# LAUNCHXL-TMS57004_RevB.net
KiCad netlist of a schematic drawn in EAGLE
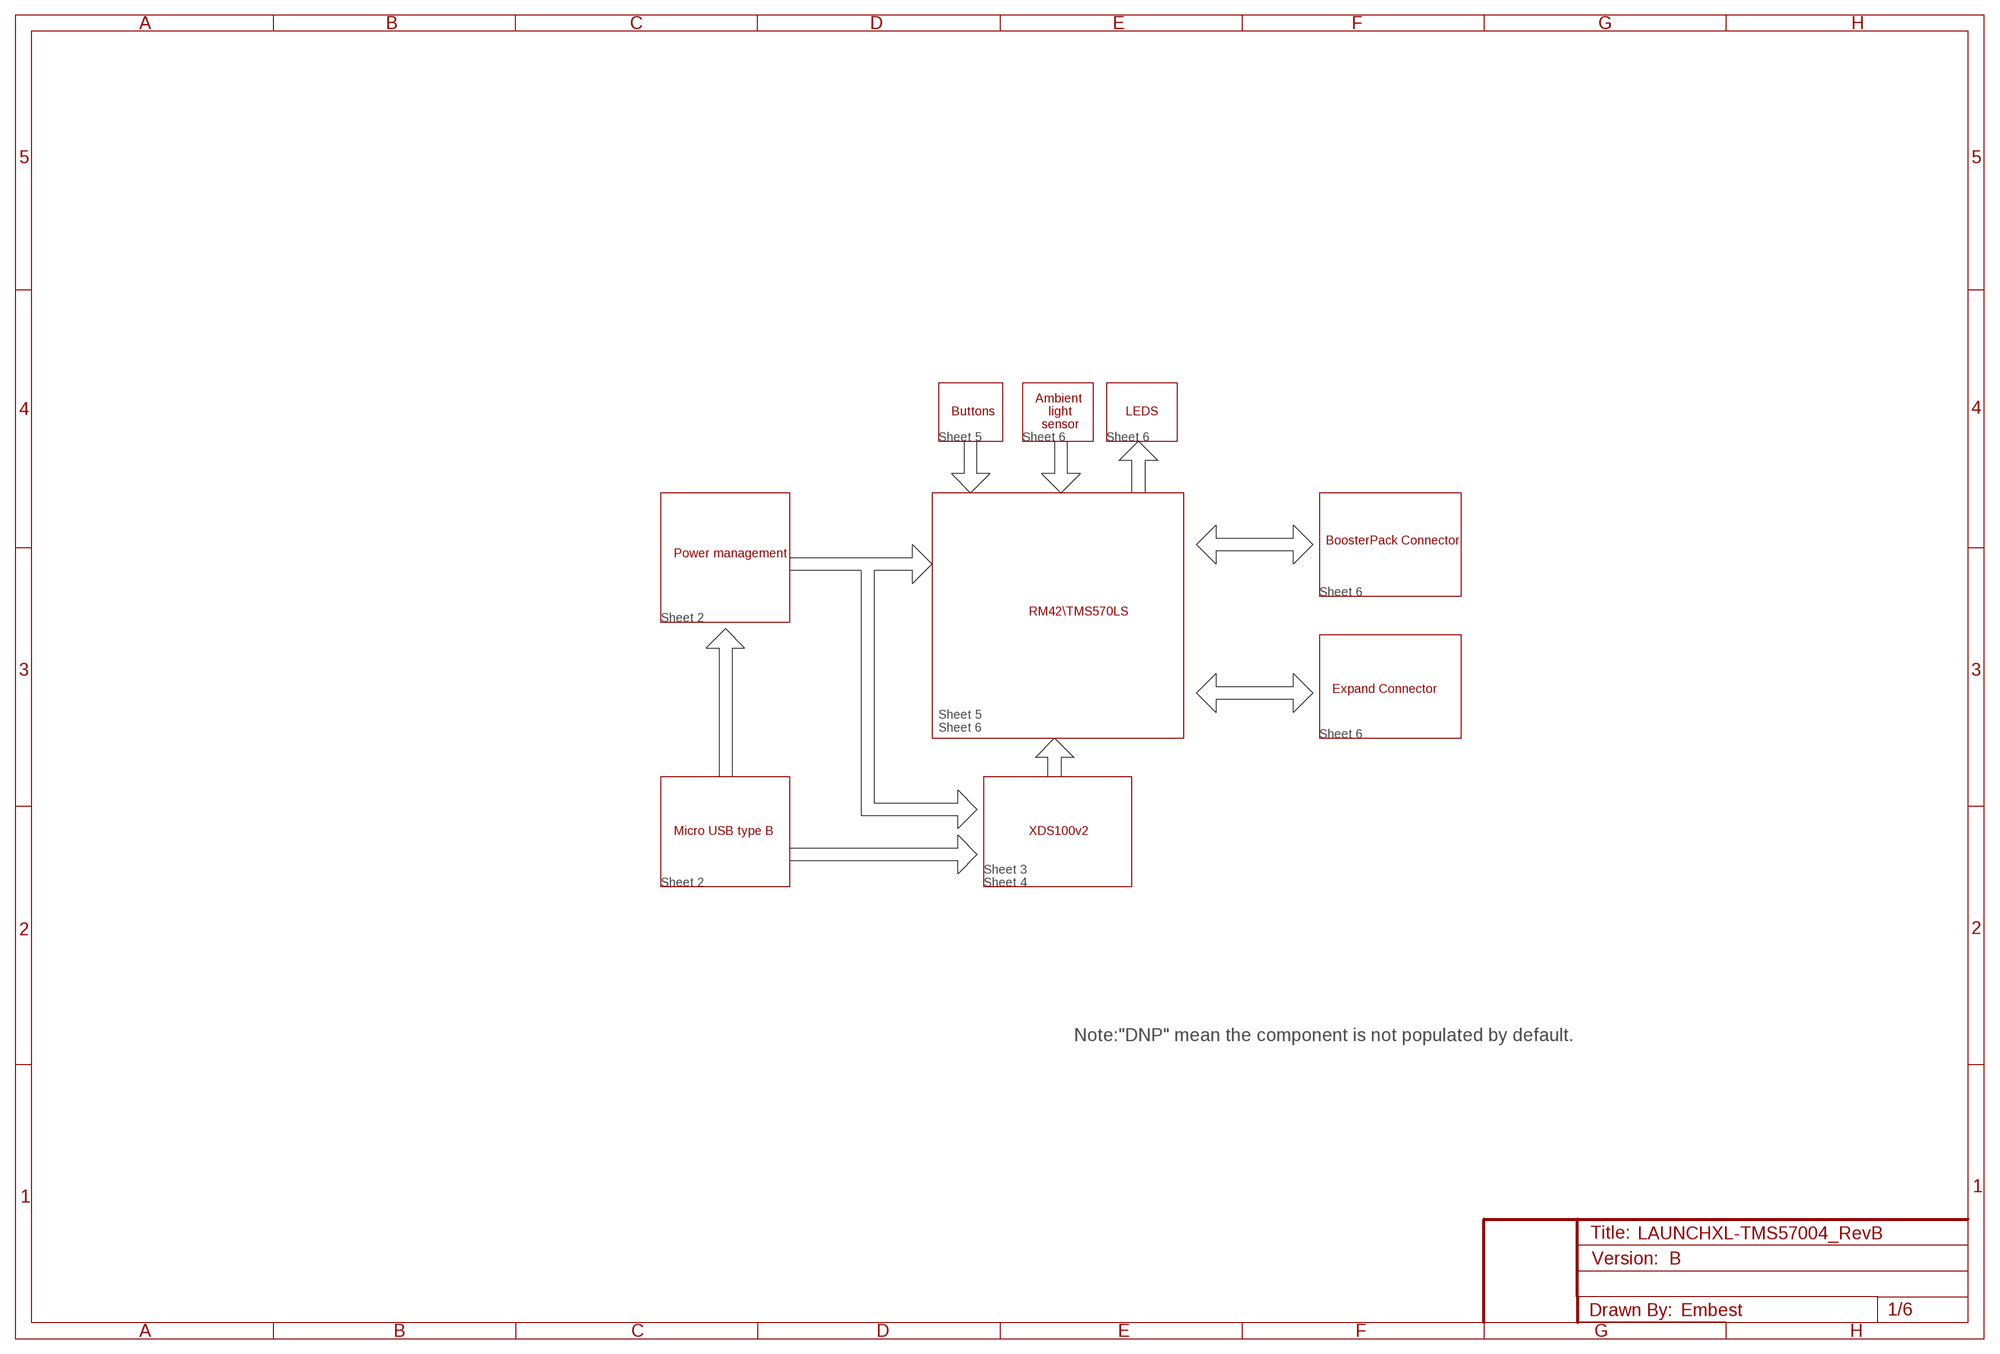
[diagram p0: schematic, sheet 1]
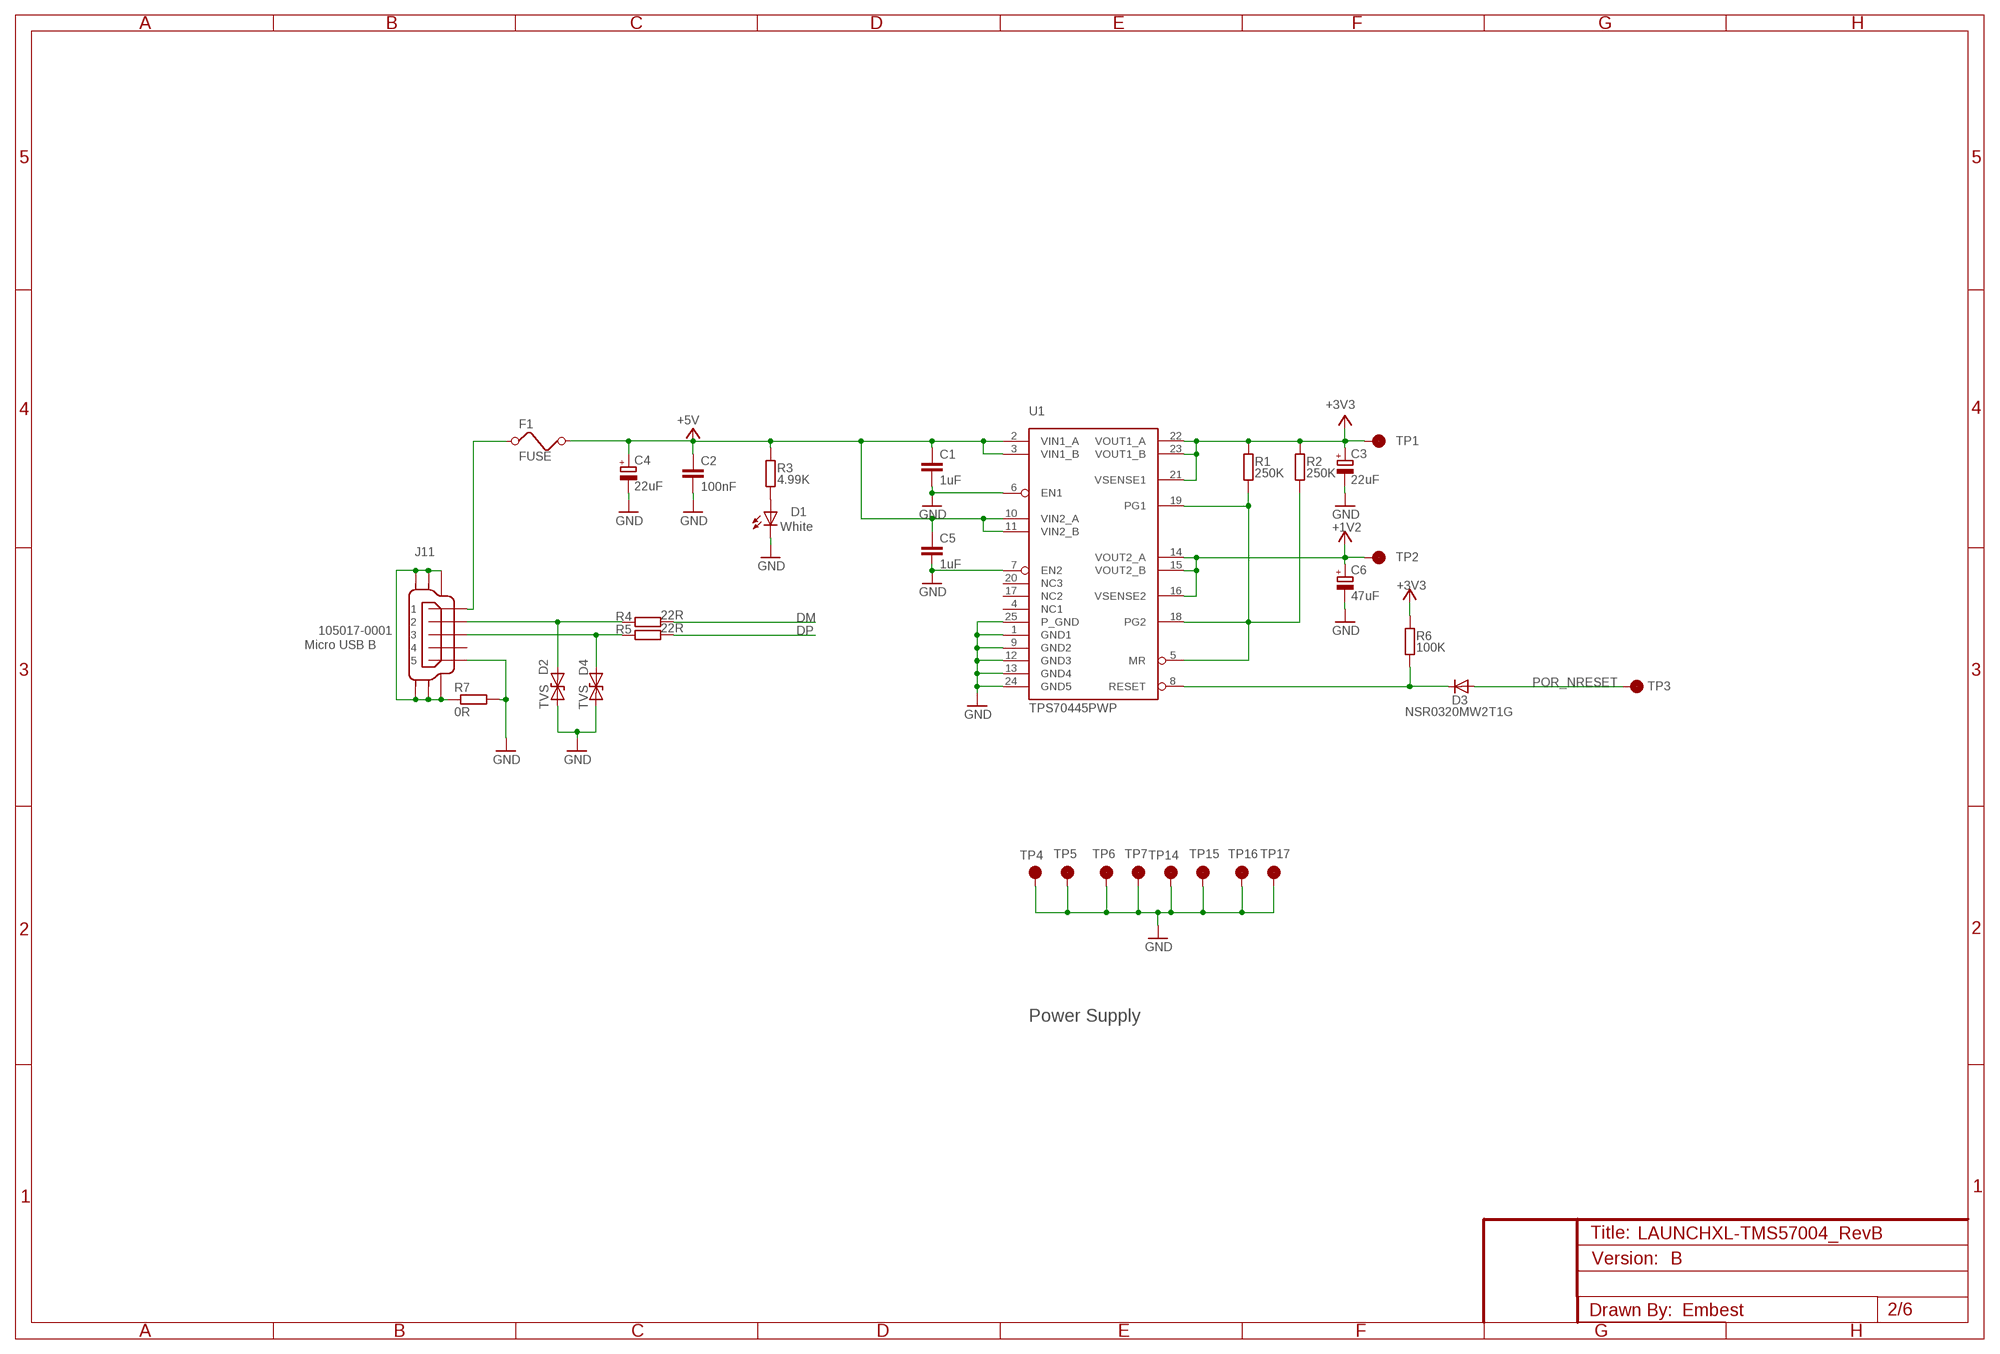
[diagram p1: schematic, sheet 2]
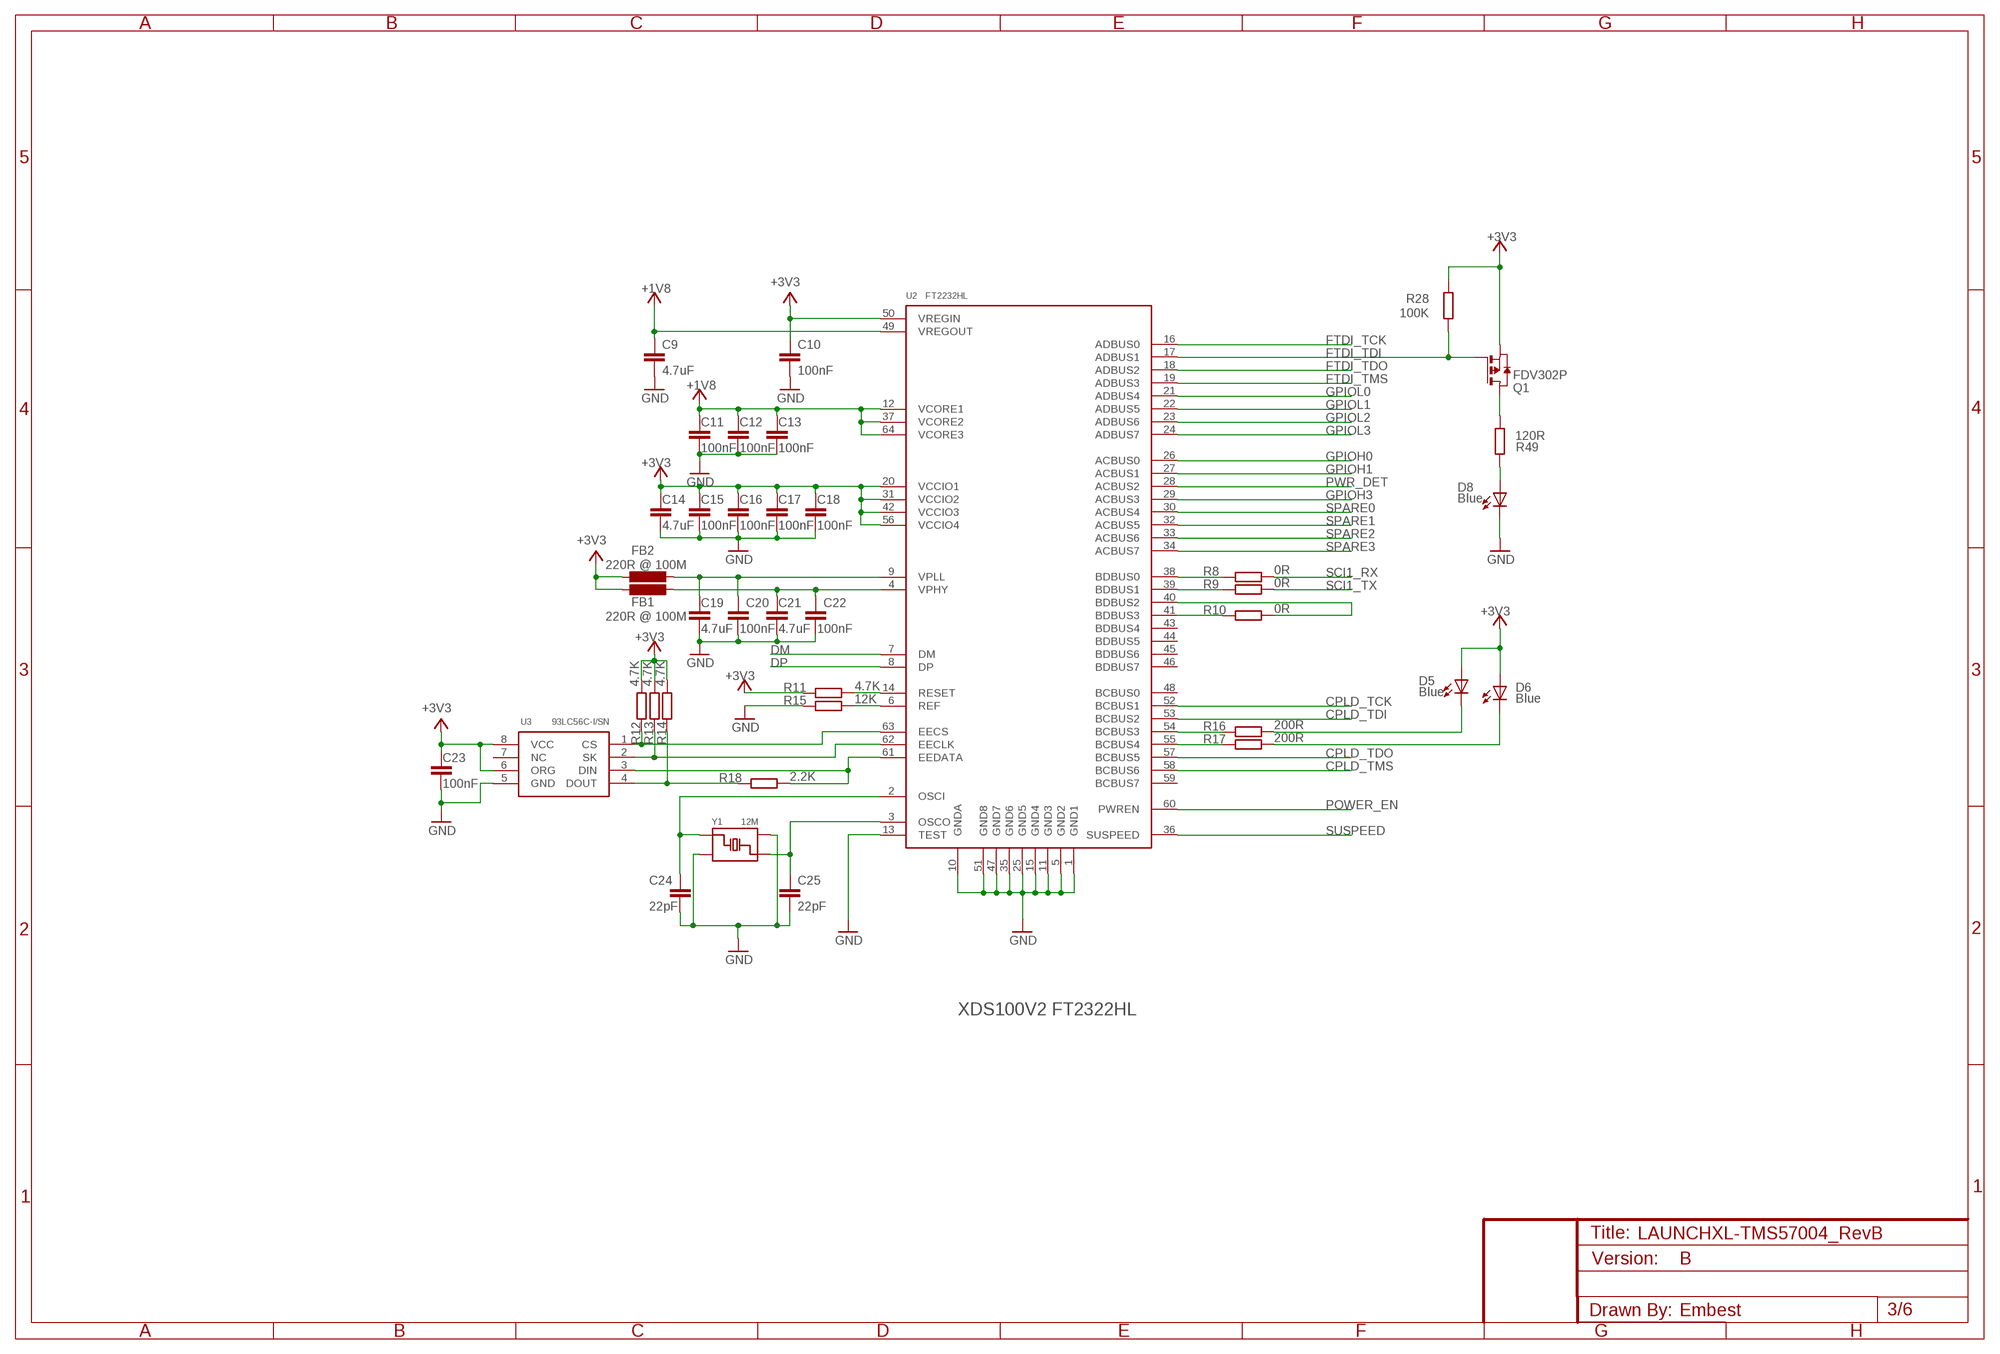
[diagram p2: schematic, sheet 3]
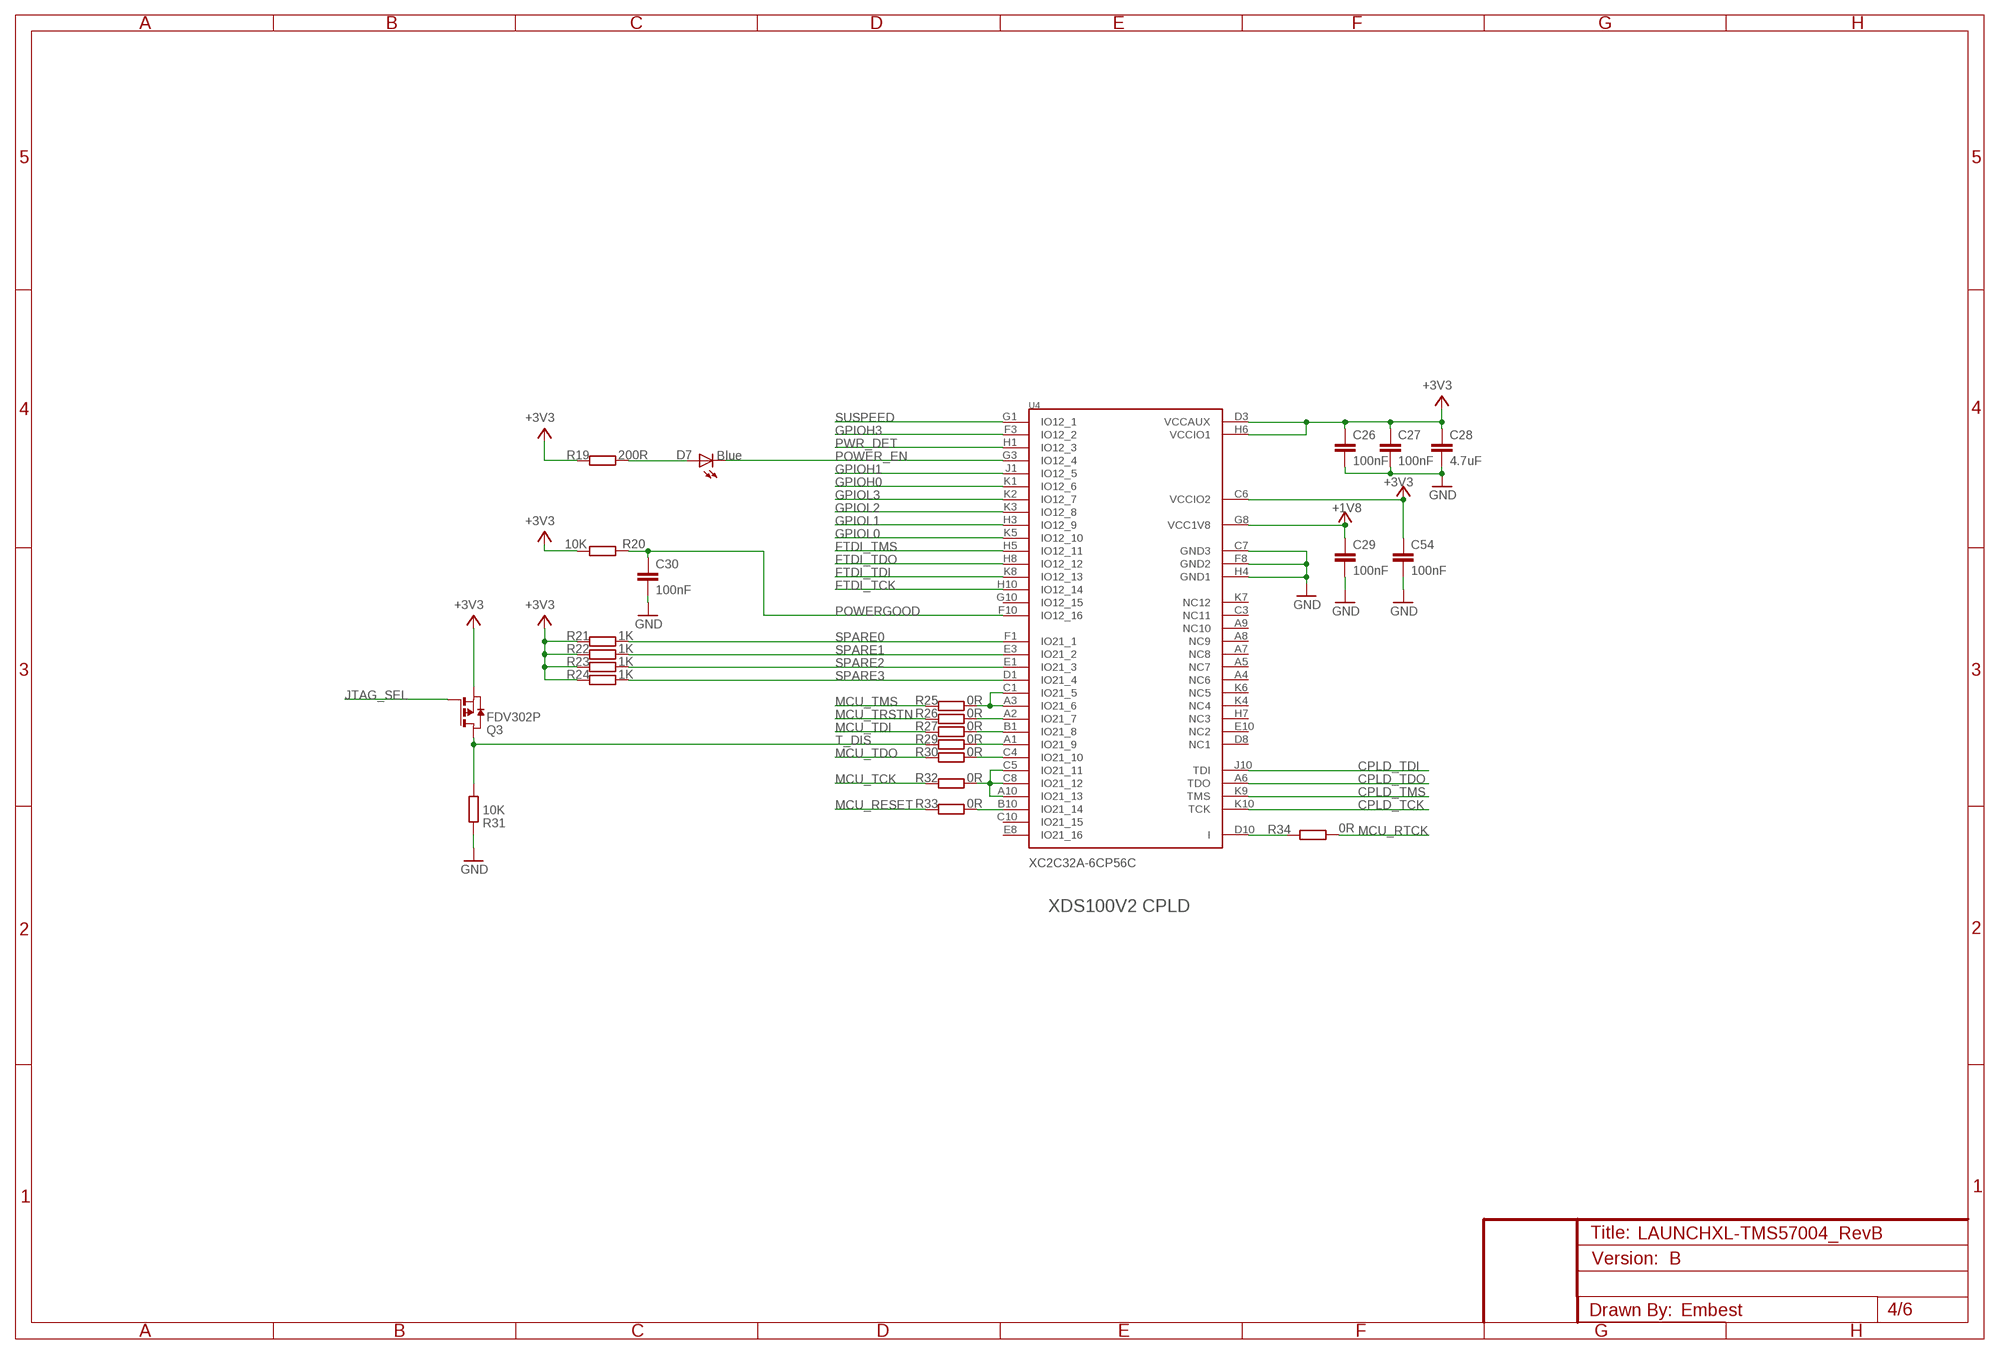
[diagram p3: schematic, sheet 4]
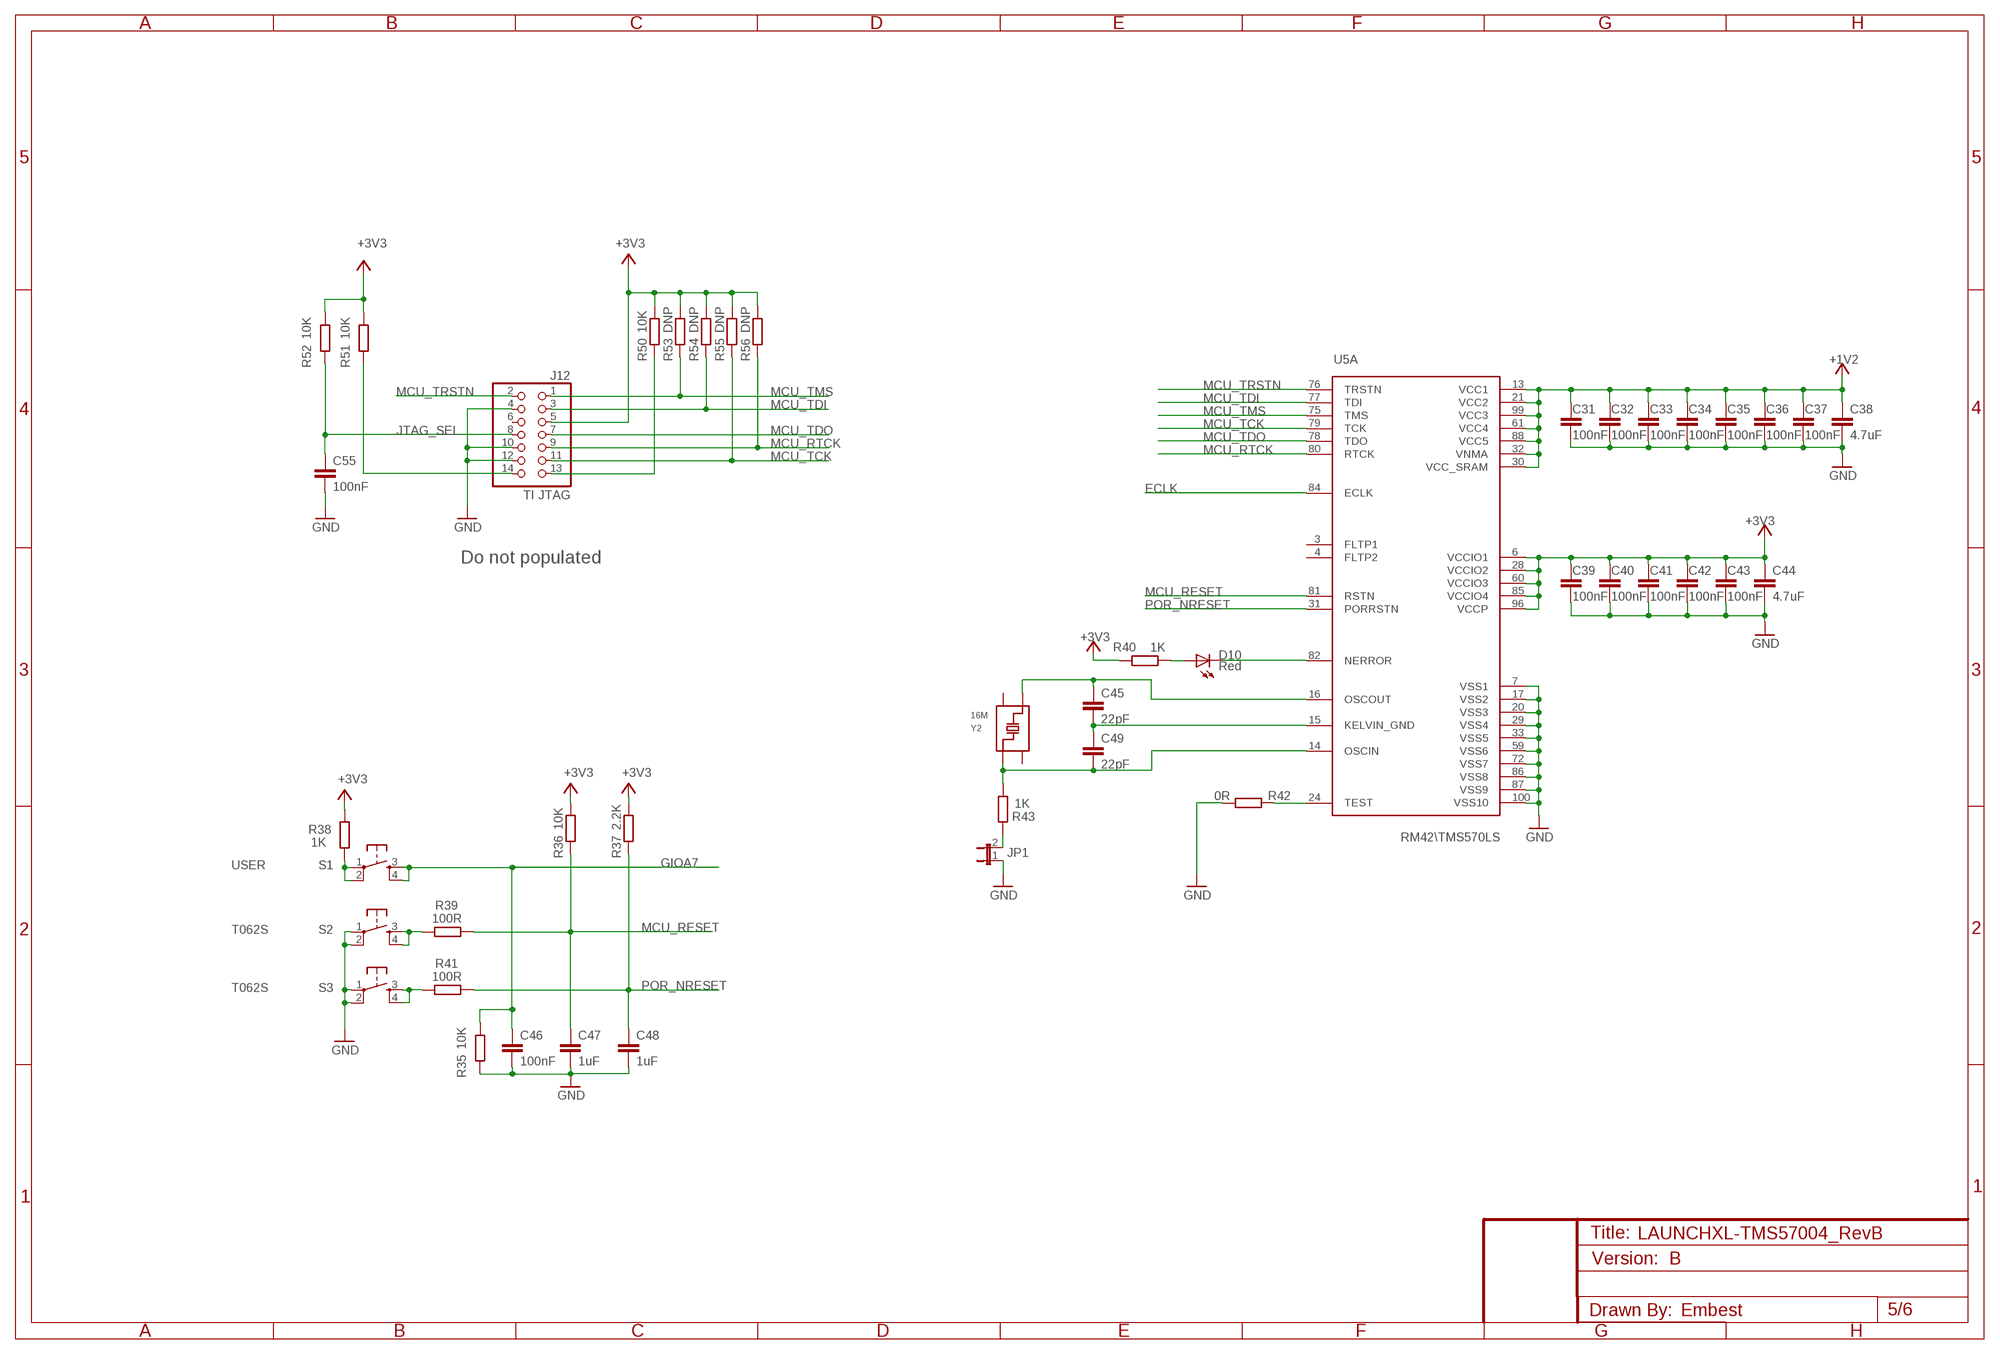
[diagram p4: schematic, sheet 5]
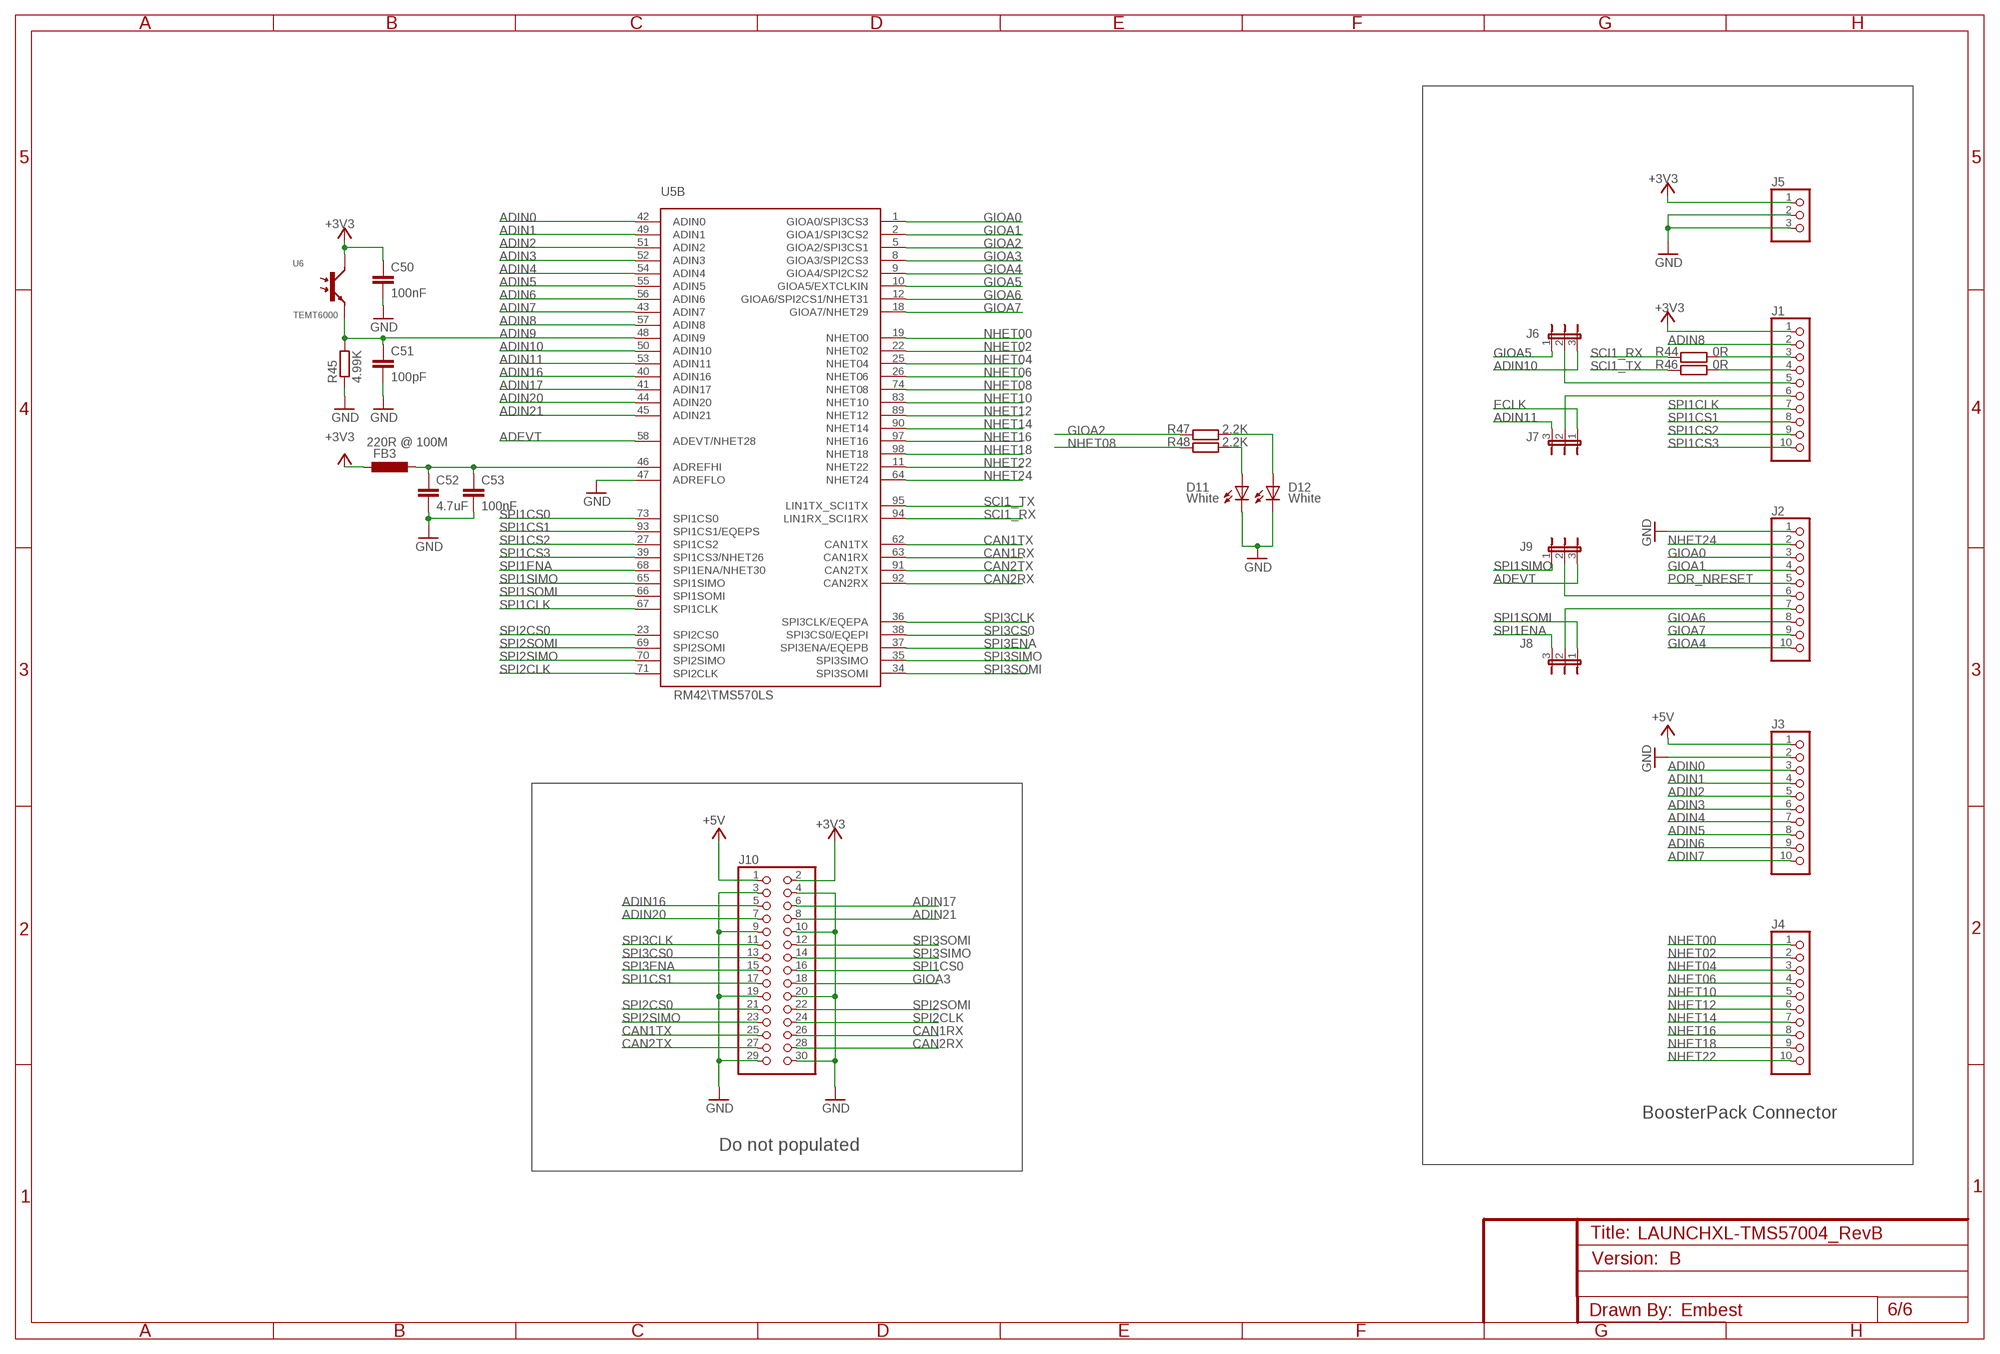
[diagram p5: schematic, sheet 6]

(export (version "E")
  (design (tool "Eeschema 10.0.6"))
  (components
    (comp (ref "C1")
      (value "1uF")
      (footprint "eagle-import:0603")
      (libsource (lib "eagle-import") (part "CAP0603"))
    )
    (comp (ref "C2")
      (value "100nF")
      (footprint "eagle-import:0402")
      (libsource (lib "eagle-import") (part "CAP0402"))
    )
    (comp (ref "C3")
      (value "22uF")
      (footprint "eagle-import:CT3528")
      (libsource (lib "eagle-import") (part "CAP-TAN"))
    )
    (comp (ref "C4")
      (value "22uF")
      (footprint "eagle-import:CT3528")
      (libsource (lib "eagle-import") (part "CAP-TAN"))
    )
    (comp (ref "C5")
      (value "1uF")
      (footprint "eagle-import:0603")
      (libsource (lib "eagle-import") (part "CAP0603"))
    )
    (comp (ref "C6")
      (value "47uF")
      (footprint "eagle-import:CT3528")
      (libsource (lib "eagle-import") (part "CAP-TAN"))
    )
    (comp (ref "D1")
      (value "White")
      (footprint "eagle-import:LED0805")
      (libsource (lib "eagle-import") (part "CHIP-LED"))
    )
    (comp (ref "D2")
      (value "TVS")
      (footprint "eagle-import:0402")
      (libsource (lib "eagle-import") (part "TVS"))
    )
    (comp (ref "D3")
      (value "NSR0320MW2T1G")
      (footprint "eagle-import:SOD-323")
      (libsource (lib "eagle-import") (part "NSR0320MW2T1G"))
    )
    (comp (ref "D4")
      (value "TVS")
      (footprint "eagle-import:0402")
      (libsource (lib "eagle-import") (part "TVS"))
    )
    (comp (ref "F1")
      (value "FUSE")
      (footprint "eagle-import:0805")
      (libsource (lib "eagle-import") (part "FUSE"))
    )
    (comp (ref "J11")
      (value "105017-0001")
      (footprint "eagle-import:MICRO_USB")
      (libsource (lib "eagle-import") (part "105017-0001"))
    )
    (comp (ref "R1")
      (value "250K")
      (footprint "eagle-import:0402")
      (libsource (lib "eagle-import") (part "RES0402"))
    )
    (comp (ref "R2")
      (value "250K")
      (footprint "eagle-import:0402")
      (libsource (lib "eagle-import") (part "RES0402"))
    )
    (comp (ref "R3")
      (value "4.99K")
      (footprint "eagle-import:0402")
      (libsource (lib "eagle-import") (part "RES0402"))
    )
    (comp (ref "R4")
      (value "22R")
      (footprint "eagle-import:0402")
      (libsource (lib "eagle-import") (part "RES0402"))
    )
    (comp (ref "R5")
      (value "22R")
      (footprint "eagle-import:0402")
      (libsource (lib "eagle-import") (part "RES0402"))
    )
    (comp (ref "R6")
      (value "100K")
      (footprint "eagle-import:0402")
      (libsource (lib "eagle-import") (part "RES0402"))
    )
    (comp (ref "R7")
      (value "0R")
      (footprint "eagle-import:0603")
      (libsource (lib "eagle-import") (part "RES0603"))
    )
    (comp (ref "TP1") (value "TP") (footprint "eagle-import:TP") (libsource (lib "eagle-import") (part "TP")))
    (comp (ref "TP2") (value "TP") (footprint "eagle-import:TP") (libsource (lib "eagle-import") (part "TP")))
    (comp (ref "TP3") (value "TP") (footprint "eagle-import:TP") (libsource (lib "eagle-import") (part "TP")))
    (comp (ref "TP4") (value "TP") (footprint "eagle-import:TP") (libsource (lib "eagle-import") (part "TP")))
    (comp (ref "TP5") (value "TP") (footprint "eagle-import:TP") (libsource (lib "eagle-import") (part "TP")))
    (comp (ref "TP6") (value "TP") (footprint "eagle-import:TP") (libsource (lib "eagle-import") (part "TP")))
    (comp (ref "TP7") (value "TP") (footprint "eagle-import:TP") (libsource (lib "eagle-import") (part "TP")))
    (comp (ref "TP14")
      (value "TP")
      (footprint "eagle-import:TP")
      (libsource (lib "eagle-import") (part "TP"))
    )
    (comp (ref "TP15")
      (value "TP")
      (footprint "eagle-import:TP")
      (libsource (lib "eagle-import") (part "TP"))
    )
    (comp (ref "TP16")
      (value "TP")
      (footprint "eagle-import:TP")
      (libsource (lib "eagle-import") (part "TP"))
    )
    (comp (ref "TP17")
      (value "TP")
      (footprint "eagle-import:TP")
      (libsource (lib "eagle-import") (part "TP"))
    )
    (comp (ref "U1")
      (value "TPS70445PWP")
      (footprint "eagle-import:TSSOP24")
      (libsource (lib "eagle-import") (part "TPS70445PWP"))
    )
    (comp (ref "C26")
      (value "100nF")
      (footprint "eagle-import:0402")
      (libsource (lib "eagle-import") (part "CAP0402"))
    )
    (comp (ref "C27")
      (value "100nF")
      (footprint "eagle-import:0402")
      (libsource (lib "eagle-import") (part "CAP0402"))
    )
    (comp (ref "C28")
      (value "4.7uF")
      (footprint "eagle-import:0805")
      (libsource (lib "eagle-import") (part "CAP0805"))
    )
    (comp (ref "C29")
      (value "100nF")
      (footprint "eagle-import:0402")
      (libsource (lib "eagle-import") (part "CAP0402"))
    )
    (comp (ref "C30")
      (value "100nF")
      (footprint "eagle-import:0402")
      (libsource (lib "eagle-import") (part "CAP0402"))
    )
    (comp (ref "C54")
      (value "100nF")
      (footprint "eagle-import:0402")
      (libsource (lib "eagle-import") (part "CAP0402"))
    )
    (comp (ref "D7")
      (value "Blue")
      (footprint "eagle-import:LED0805")
      (libsource (lib "eagle-import") (part "CHIP-LED"))
    )
    (comp (ref "Q3")
      (value "FDV302P")
      (footprint "eagle-import:SOT-23")
      (libsource (lib "eagle-import") (part "PMOSSOT23"))
    )
    (comp (ref "R19")
      (value "200R")
      (footprint "eagle-import:0402")
      (libsource (lib "eagle-import") (part "RES0402"))
    )
    (comp (ref "R20")
      (value "10K")
      (footprint "eagle-import:0402")
      (libsource (lib "eagle-import") (part "RES0402"))
    )
    (comp (ref "R21")
      (value "1K")
      (footprint "eagle-import:0402")
      (libsource (lib "eagle-import") (part "RES0402"))
    )
    (comp (ref "R22")
      (value "1K")
      (footprint "eagle-import:0402")
      (libsource (lib "eagle-import") (part "RES0402"))
    )
    (comp (ref "R23")
      (value "1K")
      (footprint "eagle-import:0402")
      (libsource (lib "eagle-import") (part "RES0402"))
    )
    (comp (ref "R24")
      (value "1K")
      (footprint "eagle-import:0402")
      (libsource (lib "eagle-import") (part "RES0402"))
    )
    (comp (ref "R25")
      (value "0R")
      (footprint "eagle-import:0402")
      (libsource (lib "eagle-import") (part "RES0402"))
    )
    (comp (ref "R26")
      (value "0R")
      (footprint "eagle-import:0402")
      (libsource (lib "eagle-import") (part "RES0402"))
    )
    (comp (ref "R27")
      (value "0R")
      (footprint "eagle-import:0402")
      (libsource (lib "eagle-import") (part "RES0402"))
    )
    (comp (ref "R29")
      (value "0R")
      (footprint "eagle-import:0402")
      (libsource (lib "eagle-import") (part "RES0402"))
    )
    (comp (ref "R30")
      (value "0R")
      (footprint "eagle-import:0402")
      (libsource (lib "eagle-import") (part "RES0402"))
    )
    (comp (ref "R31")
      (value "10K")
      (footprint "eagle-import:0402")
      (libsource (lib "eagle-import") (part "RES0402"))
    )
    (comp (ref "R32")
      (value "0R")
      (footprint "eagle-import:0402")
      (libsource (lib "eagle-import") (part "RES0402"))
    )
    (comp (ref "R33")
      (value "0R")
      (footprint "eagle-import:0402")
      (libsource (lib "eagle-import") (part "RES0402"))
    )
    (comp (ref "R34")
      (value "0R")
      (footprint "eagle-import:0402")
      (libsource (lib "eagle-import") (part "RES0402"))
    )
    (comp (ref "U4")
      (value "XC2C32A-6CP56C")
      (footprint "eagle-import:CP56")
      (libsource (lib "eagle-import") (part "XC2C32A-6CP56C"))
    )
    (comp (ref "C9")
      (value "4.7uF")
      (footprint "eagle-import:0805")
      (libsource (lib "eagle-import") (part "CAP0805"))
    )
    (comp (ref "C10")
      (value "100nF")
      (footprint "eagle-import:0402")
      (libsource (lib "eagle-import") (part "CAP0402"))
    )
    (comp (ref "C11")
      (value "100nF")
      (footprint "eagle-import:0402")
      (libsource (lib "eagle-import") (part "CAP0402"))
    )
    (comp (ref "C12")
      (value "100nF")
      (footprint "eagle-import:0402")
      (libsource (lib "eagle-import") (part "CAP0402"))
    )
    (comp (ref "C13")
      (value "100nF")
      (footprint "eagle-import:0402")
      (libsource (lib "eagle-import") (part "CAP0402"))
    )
    (comp (ref "C14")
      (value "4.7uF")
      (footprint "eagle-import:0805")
      (libsource (lib "eagle-import") (part "CAP0805"))
    )
    (comp (ref "C15")
      (value "100nF")
      (footprint "eagle-import:0402")
      (libsource (lib "eagle-import") (part "CAP0402"))
    )
    (comp (ref "C16")
      (value "100nF")
      (footprint "eagle-import:0402")
      (libsource (lib "eagle-import") (part "CAP0402"))
    )
    (comp (ref "C17")
      (value "100nF")
      (footprint "eagle-import:0402")
      (libsource (lib "eagle-import") (part "CAP0402"))
    )
    (comp (ref "C18")
      (value "100nF")
      (footprint "eagle-import:0402")
      (libsource (lib "eagle-import") (part "CAP0402"))
    )
    (comp (ref "C19")
      (value "4.7uF")
      (footprint "eagle-import:0805")
      (libsource (lib "eagle-import") (part "CAP0805"))
    )
    (comp (ref "C20")
      (value "100nF")
      (footprint "eagle-import:0402")
      (libsource (lib "eagle-import") (part "CAP0402"))
    )
    (comp (ref "C21")
      (value "4.7uF")
      (footprint "eagle-import:0805")
      (libsource (lib "eagle-import") (part "CAP0805"))
    )
    (comp (ref "C22")
      (value "100nF")
      (footprint "eagle-import:0402")
      (libsource (lib "eagle-import") (part "CAP0402"))
    )
    (comp (ref "C23")
      (value "100nF")
      (footprint "eagle-import:0402")
      (libsource (lib "eagle-import") (part "CAP0402"))
    )
    (comp (ref "C24")
      (value "22pF")
      (footprint "eagle-import:0402")
      (libsource (lib "eagle-import") (part "CAP0402"))
    )
    (comp (ref "C25")
      (value "22pF")
      (footprint "eagle-import:0402")
      (libsource (lib "eagle-import") (part "CAP0402"))
    )
    (comp (ref "D5")
      (value "Blue")
      (footprint "eagle-import:LED0805")
      (libsource (lib "eagle-import") (part "CHIP-LED"))
    )
    (comp (ref "D6")
      (value "Blue")
      (footprint "eagle-import:LED0805")
      (libsource (lib "eagle-import") (part "CHIP-LED"))
    )
    (comp (ref "D8")
      (value "Blue")
      (footprint "eagle-import:LED0805")
      (libsource (lib "eagle-import") (part "CHIP-LED"))
    )
    (comp (ref "FB1")
      (value "220R @ 100M")
      (footprint "eagle-import:0805")
      (libsource (lib "eagle-import") (part "INDUCTOR"))
    )
    (comp (ref "FB2")
      (value "220R @ 100M")
      (footprint "eagle-import:0805")
      (libsource (lib "eagle-import") (part "INDUCTOR"))
    )
    (comp (ref "Q1")
      (value "FDV302P")
      (footprint "eagle-import:SOT-23")
      (libsource (lib "eagle-import") (part "PMOSSOT23"))
    )
    (comp (ref "R8")
      (value "0R")
      (footprint "eagle-import:0402")
      (libsource (lib "eagle-import") (part "RES0402"))
    )
    (comp (ref "R9")
      (value "0R")
      (footprint "eagle-import:0402")
      (libsource (lib "eagle-import") (part "RES0402"))
    )
    (comp (ref "R10")
      (value "0R")
      (footprint "eagle-import:0402")
      (libsource (lib "eagle-import") (part "RES0402"))
    )
    (comp (ref "R11")
      (value "4.7K")
      (footprint "eagle-import:0402")
      (libsource (lib "eagle-import") (part "RES0402"))
    )
    (comp (ref "R12")
      (value "4.7K")
      (footprint "eagle-import:0402")
      (libsource (lib "eagle-import") (part "RES0402"))
    )
    (comp (ref "R13")
      (value "4.7K")
      (footprint "eagle-import:0402")
      (libsource (lib "eagle-import") (part "RES0402"))
    )
    (comp (ref "R14")
      (value "4.7K")
      (footprint "eagle-import:0402")
      (libsource (lib "eagle-import") (part "RES0402"))
    )
    (comp (ref "R15")
      (value "12K")
      (footprint "eagle-import:0402")
      (libsource (lib "eagle-import") (part "RES0402"))
    )
    (comp (ref "R16")
      (value "200R")
      (footprint "eagle-import:0402")
      (libsource (lib "eagle-import") (part "RES0402"))
    )
    (comp (ref "R17")
      (value "200R")
      (footprint "eagle-import:0402")
      (libsource (lib "eagle-import") (part "RES0402"))
    )
    (comp (ref "R18")
      (value "2.2K")
      (footprint "eagle-import:0402")
      (libsource (lib "eagle-import") (part "RES0402"))
    )
    (comp (ref "R28")
      (value "100K")
      (footprint "eagle-import:0402")
      (libsource (lib "eagle-import") (part "RES0402"))
    )
    (comp (ref "R49")
      (value "120R")
      (footprint "eagle-import:0402")
      (libsource (lib "eagle-import") (part "RES0402"))
    )
    (comp (ref "U2")
      (value "FT2232HL")
      (footprint "eagle-import:LQFP64")
      (libsource (lib "eagle-import") (part "FT2232HL"))
    )
    (comp (ref "U3")
      (value "93LC56C-I/SN")
      (footprint "eagle-import:SO8")
      (libsource (lib "eagle-import") (part "93LC56C-I/SN"))
    )
    (comp (ref "Y1")
      (value "12M")
      (footprint "eagle-import:CRYSTAL_3225")
      (libsource (lib "eagle-import") (part "CRYSTAL-SMD"))
    )
    (comp (ref "C31")
      (value "100nF")
      (footprint "eagle-import:0402")
      (libsource (lib "eagle-import") (part "CAP0402"))
    )
    (comp (ref "C32")
      (value "100nF")
      (footprint "eagle-import:0402")
      (libsource (lib "eagle-import") (part "CAP0402"))
    )
    (comp (ref "C33")
      (value "100nF")
      (footprint "eagle-import:0402")
      (libsource (lib "eagle-import") (part "CAP0402"))
    )
    (comp (ref "C34")
      (value "100nF")
      (footprint "eagle-import:0402")
      (libsource (lib "eagle-import") (part "CAP0402"))
    )
    (comp (ref "C35")
      (value "100nF")
      (footprint "eagle-import:0402")
      (libsource (lib "eagle-import") (part "CAP0402"))
    )
    (comp (ref "C36")
      (value "100nF")
      (footprint "eagle-import:0402")
      (libsource (lib "eagle-import") (part "CAP0402"))
    )
    (comp (ref "C37")
      (value "100nF")
      (footprint "eagle-import:0402")
      (libsource (lib "eagle-import") (part "CAP0402"))
    )
    (comp (ref "C38")
      (value "4.7uF")
      (footprint "eagle-import:0805")
      (libsource (lib "eagle-import") (part "CAP0805"))
    )
    (comp (ref "C39")
      (value "100nF")
      (footprint "eagle-import:0402")
      (libsource (lib "eagle-import") (part "CAP0402"))
    )
    (comp (ref "C40")
      (value "100nF")
      (footprint "eagle-import:0402")
      (libsource (lib "eagle-import") (part "CAP0402"))
    )
    (comp (ref "C41")
      (value "100nF")
      (footprint "eagle-import:0402")
      (libsource (lib "eagle-import") (part "CAP0402"))
    )
    (comp (ref "C42")
      (value "100nF")
      (footprint "eagle-import:0402")
      (libsource (lib "eagle-import") (part "CAP0402"))
    )
    (comp (ref "C43")
      (value "100nF")
      (footprint "eagle-import:0402")
      (libsource (lib "eagle-import") (part "CAP0402"))
    )
    (comp (ref "C44")
      (value "4.7uF")
      (footprint "eagle-import:0805")
      (libsource (lib "eagle-import") (part "CAP0805"))
    )
    (comp (ref "C45")
      (value "22pF")
      (footprint "eagle-import:0402")
      (libsource (lib "eagle-import") (part "CAP0402"))
    )
    (comp (ref "C46")
      (value "100nF")
      (footprint "eagle-import:0402")
      (libsource (lib "eagle-import") (part "CAP0402"))
    )
    (comp (ref "C47")
      (value "1uF")
      (footprint "eagle-import:0603")
      (libsource (lib "eagle-import") (part "CAP0603"))
    )
    (comp (ref "C48")
      (value "1uF")
      (footprint "eagle-import:0603")
      (libsource (lib "eagle-import") (part "CAP0603"))
    )
    (comp (ref "C49")
      (value "22pF")
      (footprint "eagle-import:0402")
      (libsource (lib "eagle-import") (part "CAP0402"))
    )
    (comp (ref "C55")
      (value "100nF")
      (footprint "eagle-import:0402")
      (libsource (lib "eagle-import") (part "CAP0402"))
    )
    (comp (ref "D10")
      (value "Red")
      (footprint "eagle-import:LED0805")
      (libsource (lib "eagle-import") (part "CHIP-LED"))
    )
    (comp (ref "J12")
      (value "TI JTAG")
      (footprint "eagle-import:BOXCONNECT2X7")
      (libsource (lib "eagle-import") (part "PINHEADER2X7"))
    )
    (comp (ref "JP1")
      (value "JUMPER_2.51MM")
      (footprint "eagle-import:JUMPER-2.54")
      (libsource (lib "eagle-import") (part "JUMPER_2.51MM"))
    )
    (comp (ref "R35")
      (value "10K")
      (footprint "eagle-import:0402")
      (libsource (lib "eagle-import") (part "RES0402"))
    )
    (comp (ref "R36")
      (value "10K")
      (footprint "eagle-import:0402")
      (libsource (lib "eagle-import") (part "RES0402"))
    )
    (comp (ref "R37")
      (value "2.2K")
      (footprint "eagle-import:0402")
      (libsource (lib "eagle-import") (part "RES0402"))
    )
    (comp (ref "R38")
      (value "1K")
      (footprint "eagle-import:0402")
      (libsource (lib "eagle-import") (part "RES0402"))
    )
    (comp (ref "R39")
      (value "100R")
      (footprint "eagle-import:0402")
      (libsource (lib "eagle-import") (part "RES0402"))
    )
    (comp (ref "R40")
      (value "1K")
      (footprint "eagle-import:0402")
      (libsource (lib "eagle-import") (part "RES0402"))
    )
    (comp (ref "R41")
      (value "100R")
      (footprint "eagle-import:0402")
      (libsource (lib "eagle-import") (part "RES0402"))
    )
    (comp (ref "R42")
      (value "0R")
      (footprint "eagle-import:0402")
      (libsource (lib "eagle-import") (part "RES0402"))
    )
    (comp (ref "R43")
      (value "1K")
      (footprint "eagle-import:0402")
      (libsource (lib "eagle-import") (part "RES0402"))
    )
    (comp (ref "R50")
      (value "10K")
      (footprint "eagle-import:0402")
      (libsource (lib "eagle-import") (part "RES0402"))
    )
    (comp (ref "R51")
      (value "10K")
      (footprint "eagle-import:0402")
      (libsource (lib "eagle-import") (part "RES0402"))
    )
    (comp (ref "R52")
      (value "10K")
      (footprint "eagle-import:0402")
      (libsource (lib "eagle-import") (part "RES0402"))
    )
    (comp (ref "R53")
      (value "DNP")
      (footprint "eagle-import:0402")
      (libsource (lib "eagle-import") (part "RES0402"))
    )
    (comp (ref "R54")
      (value "DNP")
      (footprint "eagle-import:0402")
      (libsource (lib "eagle-import") (part "RES0402"))
    )
    (comp (ref "R55")
      (value "DNP")
      (footprint "eagle-import:0402")
      (libsource (lib "eagle-import") (part "RES0402"))
    )
    (comp (ref "R56")
      (value "DNP")
      (footprint "eagle-import:0402")
      (libsource (lib "eagle-import") (part "RES0402"))
    )
    (comp (ref "S1")
      (value "USER")
      (footprint "eagle-import:T062S")
      (libsource (lib "eagle-import") (part "T062S"))
    )
    (comp (ref "S2")
      (value "T062S")
      (footprint "eagle-import:T062S")
      (libsource (lib "eagle-import") (part "T062S"))
    )
    (comp (ref "S3")
      (value "T062S")
      (footprint "eagle-import:T062S")
      (libsource (lib "eagle-import") (part "T062S"))
    )
    (comp (ref "U5")
      (value "RM42\\\\TMS570LS")
      (footprint "eagle-import:LQFP100")
      (libsource (lib "eagle-import") (part "RM42L432"))
    )
    (comp (ref "Y2")
      (value "16M")
      (footprint "eagle-import:CRYSTAL_3225")
      (libsource (lib "eagle-import") (part "CRYSTAL-SMD"))
    )
    (comp (ref "C50")
      (value "100nF")
      (footprint "eagle-import:0402")
      (libsource (lib "eagle-import") (part "CAP0402"))
    )
    (comp (ref "C51")
      (value "100pF")
      (footprint "eagle-import:0402")
      (libsource (lib "eagle-import") (part "CAP0402"))
    )
    (comp (ref "C52")
      (value "4.7uF")
      (footprint "eagle-import:0805")
      (libsource (lib "eagle-import") (part "CAP0805"))
    )
    (comp (ref "C53")
      (value "100nF")
      (footprint "eagle-import:0402")
      (libsource (lib "eagle-import") (part "CAP0402"))
    )
    (comp (ref "D11")
      (value "White")
      (footprint "eagle-import:LED0805")
      (libsource (lib "eagle-import") (part "CHIP-LED"))
    )
    (comp (ref "D12")
      (value "White")
      (footprint "eagle-import:LED0805")
      (libsource (lib "eagle-import") (part "CHIP-LED"))
    )
    (comp (ref "FB3")
      (value "220R @ 100M")
      (footprint "eagle-import:0805")
      (libsource (lib "eagle-import") (part "INDUCTOR"))
    )
    (comp (ref "J1")
      (value "PINHEADER1X10")
      (footprint "eagle-import:PINHEAFER1X10")
      (libsource (lib "eagle-import") (part "PINHEADER1X10"))
    )
    (comp (ref "J2")
      (value "PINHEADER1X10")
      (footprint "eagle-import:PINHEAFER1X10")
      (libsource (lib "eagle-import") (part "PINHEADER1X10"))
    )
    (comp (ref "J3")
      (value "PINHEADER1X10")
      (footprint "eagle-import:PINHEAFER1X10")
      (libsource (lib "eagle-import") (part "PINHEADER1X10"))
    )
    (comp (ref "J4")
      (value "PINHEADER1X10")
      (footprint "eagle-import:PINHEAFER1X10")
      (libsource (lib "eagle-import") (part "PINHEADER1X10"))
    )
    (comp (ref "J5")
      (value "PINHEADER1X3")
      (footprint "eagle-import:PINHEADER1X3")
      (libsource (lib "eagle-import") (part "PINHEADER1X3"))
    )
    (comp (ref "J6")
      (value "HEADER3-100")
      (footprint "eagle-import:HEADER3-100")
      (libsource (lib "eagle-import") (part "HEADER3-100"))
    )
    (comp (ref "J7")
      (value "HEADER3-100")
      (footprint "eagle-import:HEADER3-100")
      (libsource (lib "eagle-import") (part "HEADER3-100"))
    )
    (comp (ref "J8")
      (value "HEADER3-100")
      (footprint "eagle-import:HEADER3-100")
      (libsource (lib "eagle-import") (part "HEADER3-100"))
    )
    (comp (ref "J9")
      (value "HEADER3-100")
      (footprint "eagle-import:HEADER3-100")
      (libsource (lib "eagle-import") (part "HEADER3-100"))
    )
    (comp (ref "J10")
      (value "PINHD-2X15")
      (footprint "eagle-import:2X15")
      (libsource (lib "eagle-import") (part "PINHD-2X15"))
    )
    (comp (ref "R44")
      (value "0R")
      (footprint "eagle-import:0402")
      (libsource (lib "eagle-import") (part "RES0402"))
    )
    (comp (ref "R45")
      (value "4.99K")
      (footprint "eagle-import:0402")
      (libsource (lib "eagle-import") (part "RES0402"))
    )
    (comp (ref "R46")
      (value "0R")
      (footprint "eagle-import:0402")
      (libsource (lib "eagle-import") (part "RES0402"))
    )
    (comp (ref "R47")
      (value "2.2K")
      (footprint "eagle-import:0402")
      (libsource (lib "eagle-import") (part "RES0402"))
    )
    (comp (ref "R48")
      (value "2.2K")
      (footprint "eagle-import:0402")
      (libsource (lib "eagle-import") (part "RES0402"))
    )
    (comp (ref "U6")
      (value "TEMT6000")
      (footprint "eagle-import:TEMT6000")
      (libsource (lib "eagle-import") (part "TEMT6000"))
    )
  )
  (nets
    (net (code "1") (name "+1V8") (class "Default")
      (node (ref "C11") (pin "1") (pinfunction "1_1") (pintype "passive"))
      (node (ref "C12") (pin "1") (pinfunction "1_1") (pintype "passive"))
      (node (ref "C13") (pin "1") (pinfunction "1_1") (pintype "passive"))
      (node (ref "C29") (pin "1") (pinfunction "1_1") (pintype "passive"))
      (node (ref "C9") (pin "1") (pinfunction "1_1") (pintype "passive"))
      (node (ref "U2") (pin "12") (pinfunction "VCORE1_12") (pintype "bidirectional"))
      (node (ref "U2") (pin "37") (pinfunction "VCORE2_37") (pintype "bidirectional"))
      (node (ref "U2") (pin "49") (pinfunction "VREGOUT_49") (pintype "bidirectional"))
      (node (ref "U2") (pin "64") (pinfunction "VCORE3_64") (pintype "bidirectional"))
      (node (ref "U4") (pin "G8") (pinfunction "VCC1V8_G8") (pintype "bidirectional"))
    )
    (net (code "2") (name "+3V3") (class "Default")
      (node (ref "C10") (pin "1") (pinfunction "1_1") (pintype "passive"))
      (node (ref "C14") (pin "1") (pinfunction "1_1") (pintype "passive"))
      (node (ref "C15") (pin "1") (pinfunction "1_1") (pintype "passive"))
      (node (ref "C16") (pin "1") (pinfunction "1_1") (pintype "passive"))
      (node (ref "C17") (pin "1") (pinfunction "1_1") (pintype "passive"))
      (node (ref "C18") (pin "1") (pinfunction "1_1") (pintype "passive"))
      (node (ref "C23") (pin "1") (pinfunction "1_1") (pintype "passive"))
      (node (ref "C26") (pin "1") (pinfunction "1_1") (pintype "passive"))
      (node (ref "C27") (pin "1") (pinfunction "1_1") (pintype "passive"))
      (node (ref "C28") (pin "1") (pinfunction "1_1") (pintype "passive"))
      (node (ref "C3") (pin "+") (pinfunction "+_+") (pintype "passive"))
      (node (ref "C39") (pin "1") (pinfunction "1_1") (pintype "passive"))
      (node (ref "C40") (pin "1") (pinfunction "1_1") (pintype "passive"))
      (node (ref "C41") (pin "1") (pinfunction "1_1") (pintype "passive"))
      (node (ref "C42") (pin "1") (pinfunction "1_1") (pintype "passive"))
      (node (ref "C43") (pin "1") (pinfunction "1_1") (pintype "passive"))
      (node (ref "C44") (pin "1") (pinfunction "1_1") (pintype "passive"))
      (node (ref "C50") (pin "1") (pinfunction "1_1") (pintype "passive"))
      (node (ref "C54") (pin "1") (pinfunction "1_1") (pintype "passive"))
      (node (ref "D5") (pin "A") (pinfunction "A_A") (pintype "passive"))
      (node (ref "D6") (pin "A") (pinfunction "A_A") (pintype "passive"))
      (node (ref "FB1") (pin "1") (pinfunction "1_1") (pintype "passive"))
      (node (ref "FB2") (pin "1") (pinfunction "1_1") (pintype "passive"))
      (node (ref "FB3") (pin "1") (pinfunction "1_1") (pintype "passive"))
      (node (ref "J1") (pin "1") (pinfunction "1_1") (pintype "passive"))
      (node (ref "J10") (pin "2") (pinfunction "2_2") (pintype "passive"))
      (node (ref "J12") (pin "5") (pinfunction "5_5") (pintype "passive"))
      (node (ref "J5") (pin "1") (pinfunction "1_1") (pintype "passive"))
      (node (ref "Q1") (pin "2") (pinfunction "S_2") (pintype "passive"))
      (node (ref "Q3") (pin "2") (pinfunction "S_2") (pintype "passive"))
      (node (ref "R1") (pin "2") (pinfunction "2_2") (pintype "passive"))
      (node (ref "R11") (pin "1") (pinfunction "1_1") (pintype "passive"))
      (node (ref "R12") (pin "2") (pinfunction "2_2") (pintype "passive"))
      (node (ref "R13") (pin "2") (pinfunction "2_2") (pintype "passive"))
      (node (ref "R14") (pin "2") (pinfunction "2_2") (pintype "passive"))
      (node (ref "R19") (pin "1") (pinfunction "1_1") (pintype "passive"))
      (node (ref "R2") (pin "2") (pinfunction "2_2") (pintype "passive"))
      (node (ref "R20") (pin "2") (pinfunction "2_2") (pintype "passive"))
      (node (ref "R21") (pin "1") (pinfunction "1_1") (pintype "passive"))
      (node (ref "R22") (pin "1") (pinfunction "1_1") (pintype "passive"))
      (node (ref "R23") (pin "1") (pinfunction "1_1") (pintype "passive"))
      (node (ref "R24") (pin "1") (pinfunction "1_1") (pintype "passive"))
      (node (ref "R28") (pin "2") (pinfunction "2_2") (pintype "passive"))
      (node (ref "R36") (pin "2") (pinfunction "2_2") (pintype "passive"))
      (node (ref "R37") (pin "2") (pinfunction "2_2") (pintype "passive"))
      (node (ref "R38") (pin "1") (pinfunction "1_1") (pintype "passive"))
      (node (ref "R40") (pin "2") (pinfunction "2_2") (pintype "passive"))
      (node (ref "R50") (pin "2") (pinfunction "2_2") (pintype "passive"))
      (node (ref "R51") (pin "2") (pinfunction "2_2") (pintype "passive"))
      (node (ref "R52") (pin "2") (pinfunction "2_2") (pintype "passive"))
      (node (ref "R53") (pin "2") (pinfunction "2_2") (pintype "passive"))
      (node (ref "R54") (pin "2") (pinfunction "2_2") (pintype "passive"))
      (node (ref "R55") (pin "2") (pinfunction "2_2") (pintype "passive"))
      (node (ref "R56") (pin "2") (pinfunction "2_2") (pintype "passive"))
      (node (ref "R6") (pin "2") (pinfunction "2_2") (pintype "passive"))
      (node (ref "TP1") (pin "1") (pinfunction "P$1_1") (pintype "bidirectional"))
      (node (ref "U1") (pin "21") (pinfunction "VSENSE1_21") (pintype "input"))
      (node (ref "U1") (pin "22") (pinfunction "VOUT1_A_22") (pintype "passive"))
      (node (ref "U1") (pin "23") (pinfunction "VOUT1_B_23") (pintype "passive"))
      (node (ref "U2") (pin "20") (pinfunction "VCCIO1_20") (pintype "bidirectional"))
      (node (ref "U2") (pin "31") (pinfunction "VCCIO2_31") (pintype "bidirectional"))
      (node (ref "U2") (pin "42") (pinfunction "VCCIO3_42") (pintype "bidirectional"))
      (node (ref "U2") (pin "50") (pinfunction "VREGIN_50") (pintype "bidirectional"))
      (node (ref "U2") (pin "56") (pinfunction "VCCIO4_56") (pintype "bidirectional"))
      (node (ref "U3") (pin "6") (pinfunction "ORG_6") (pintype "bidirectional"))
      (node (ref "U3") (pin "8") (pinfunction "VCC_8") (pintype "bidirectional"))
      (node (ref "U4") (pin "C6") (pinfunction "VCCIO2_C6") (pintype "bidirectional"))
      (node (ref "U4") (pin "D3") (pinfunction "VCCAUX_D3") (pintype "bidirectional"))
      (node (ref "U4") (pin "H6") (pinfunction "VCCIO1_H6") (pintype "bidirectional"))
      (node (ref "U5") (pin "28") (pinfunction "VCCIO2_28") (pintype "bidirectional"))
      (node (ref "U5") (pin "6") (pinfunction "VCCIO1_6") (pintype "bidirectional"))
      (node (ref "U5") (pin "60") (pinfunction "VCCIO3_60") (pintype "bidirectional"))
      (node (ref "U5") (pin "85") (pinfunction "VCCIO4_85") (pintype "bidirectional"))
      (node (ref "U5") (pin "96") (pinfunction "VCCP_96") (pintype "bidirectional"))
      (node (ref "U6") (pin "3") (pinfunction "C_3") (pintype "bidirectional"))
    )
    (net (code "3") (name "+5V") (class "Default")
      (node (ref "C1") (pin "1") (pinfunction "1_1") (pintype "passive"))
      (node (ref "C2") (pin "1") (pinfunction "1_1") (pintype "passive"))
      (node (ref "C4") (pin "+") (pinfunction "+_+") (pintype "passive"))
      (node (ref "C5") (pin "1") (pinfunction "1_1") (pintype "passive"))
      (node (ref "F1") (pin "2") (pinfunction "2_2") (pintype "passive"))
      (node (ref "J10") (pin "1") (pinfunction "1_1") (pintype "passive"))
      (node (ref "J3") (pin "1") (pinfunction "1_1") (pintype "passive"))
      (node (ref "R3") (pin "2") (pinfunction "2_2") (pintype "passive"))
      (node (ref "U1") (pin "10") (pinfunction "VIN2_A_10") (pintype "passive"))
      (node (ref "U1") (pin "11") (pinfunction "VIN2_B_11") (pintype "passive"))
      (node (ref "U1") (pin "2") (pinfunction "VIN1_A_2") (pintype "passive"))
      (node (ref "U1") (pin "3") (pinfunction "VIN1_B_3") (pintype "passive"))
    )
    (net (code "4") (name "ADEVT") (class "Default")
      (node (ref "J9") (pin "3") (pinfunction "3_3") (pintype "passive"))
      (node (ref "U5") (pin "58") (pinfunction "ADEVT/NHET28_58") (pintype "bidirectional"))
    )
    (net (code "5") (name "ADIN0") (class "Default")
      (node (ref "J3") (pin "3") (pinfunction "3_3") (pintype "passive"))
      (node (ref "U5") (pin "42") (pinfunction "ADIN0_42") (pintype "bidirectional"))
    )
    (net (code "6") (name "ADIN1") (class "Default")
      (node (ref "J3") (pin "4") (pinfunction "4_4") (pintype "passive"))
      (node (ref "U5") (pin "49") (pinfunction "ADIN1_49") (pintype "bidirectional"))
    )
    (net (code "7") (name "ADIN2") (class "Default")
      (node (ref "J3") (pin "5") (pinfunction "5_5") (pintype "passive"))
      (node (ref "U5") (pin "51") (pinfunction "ADIN2_51") (pintype "bidirectional"))
    )
    (net (code "8") (name "ADIN3") (class "Default")
      (node (ref "J3") (pin "6") (pinfunction "6_6") (pintype "passive"))
      (node (ref "U5") (pin "52") (pinfunction "ADIN3_52") (pintype "bidirectional"))
    )
    (net (code "9") (name "ADIN4") (class "Default")
      (node (ref "J3") (pin "7") (pinfunction "7_7") (pintype "passive"))
      (node (ref "U5") (pin "54") (pinfunction "ADIN4_54") (pintype "bidirectional"))
    )
    (net (code "10") (name "ADIN5") (class "Default")
      (node (ref "J3") (pin "8") (pinfunction "8_8") (pintype "passive"))
      (node (ref "U5") (pin "55") (pinfunction "ADIN5_55") (pintype "bidirectional"))
    )
    (net (code "11") (name "ADIN6") (class "Default")
      (node (ref "J3") (pin "9") (pinfunction "9_9") (pintype "passive"))
      (node (ref "U5") (pin "56") (pinfunction "ADIN6_56") (pintype "bidirectional"))
    )
    (net (code "12") (name "ADIN7") (class "Default")
      (node (ref "J3") (pin "10") (pinfunction "10_10") (pintype "passive"))
      (node (ref "U5") (pin "43") (pinfunction "ADIN7_43") (pintype "bidirectional"))
    )
    (net (code "13") (name "ADIN8") (class "Default")
      (node (ref "J1") (pin "2") (pinfunction "2_2") (pintype "passive"))
      (node (ref "U5") (pin "57") (pinfunction "ADIN8_57") (pintype "bidirectional"))
    )
    (net (code "14") (name "ADIN9") (class "Default")
      (node (ref "C51") (pin "1") (pinfunction "1_1") (pintype "passive"))
      (node (ref "R45") (pin "2") (pinfunction "2_2") (pintype "passive"))
      (node (ref "U5") (pin "48") (pinfunction "ADIN9_48") (pintype "bidirectional"))
      (node (ref "U6") (pin "1") (pinfunction "E_1") (pintype "bidirectional"))
    )
    (net (code "15") (name "ADIN10") (class "Default")
      (node (ref "J6") (pin "3") (pinfunction "3_3") (pintype "passive"))
      (node (ref "U5") (pin "50") (pinfunction "ADIN10_50") (pintype "bidirectional"))
    )
    (net (code "16") (name "ADIN11") (class "Default")
      (node (ref "J7") (pin "3") (pinfunction "3_3") (pintype "passive"))
      (node (ref "U5") (pin "53") (pinfunction "ADIN11_53") (pintype "bidirectional"))
    )
    (net (code "17") (name "ADIN16") (class "Default")
      (node (ref "J10") (pin "5") (pinfunction "5_5") (pintype "passive"))
      (node (ref "U5") (pin "40") (pinfunction "ADIN16_40") (pintype "bidirectional"))
    )
    (net (code "18") (name "ADIN17") (class "Default")
      (node (ref "J10") (pin "6") (pinfunction "6_6") (pintype "passive"))
      (node (ref "U5") (pin "41") (pinfunction "ADIN17_41") (pintype "bidirectional"))
    )
    (net (code "19") (name "ADIN20") (class "Default")
      (node (ref "J10") (pin "7") (pinfunction "7_7") (pintype "passive"))
      (node (ref "U5") (pin "44") (pinfunction "ADIN20_44") (pintype "bidirectional"))
    )
    (net (code "20") (name "ADIN21") (class "Default")
      (node (ref "J10") (pin "8") (pinfunction "8_8") (pintype "passive"))
      (node (ref "U5") (pin "45") (pinfunction "ADIN21_45") (pintype "bidirectional"))
    )
    (net (code "21") (name "CAN1RX") (class "Default")
      (node (ref "J10") (pin "26") (pinfunction "26_26") (pintype "passive"))
      (node (ref "U5") (pin "63") (pinfunction "CAN1RX_63") (pintype "bidirectional"))
    )
    (net (code "22") (name "CAN1TX") (class "Default")
      (node (ref "J10") (pin "25") (pinfunction "25_25") (pintype "passive"))
      (node (ref "U5") (pin "62") (pinfunction "CAN1TX_62") (pintype "bidirectional"))
    )
    (net (code "23") (name "CAN2RX") (class "Default")
      (node (ref "J10") (pin "28") (pinfunction "28_28") (pintype "passive"))
      (node (ref "U5") (pin "92") (pinfunction "CAN2RX_92") (pintype "bidirectional"))
    )
    (net (code "24") (name "CAN2TX") (class "Default")
      (node (ref "J10") (pin "27") (pinfunction "27_27") (pintype "passive"))
      (node (ref "U5") (pin "91") (pinfunction "CAN2TX_91") (pintype "bidirectional"))
    )
    (net (code "25") (name "CPLD_TCK") (class "Default")
      (node (ref "U2") (pin "52") (pinfunction "BCBUS1_52") (pintype "bidirectional"))
      (node (ref "U4") (pin "K10") (pinfunction "TCK_K10") (pintype "bidirectional"))
    )
    (net (code "26") (name "CPLD_TDI") (class "Default")
      (node (ref "U2") (pin "53") (pinfunction "BCBUS2_53") (pintype "bidirectional"))
      (node (ref "U4") (pin "J10") (pinfunction "TDI_J10") (pintype "bidirectional"))
    )
    (net (code "27") (name "CPLD_TDO") (class "Default")
      (node (ref "U2") (pin "57") (pinfunction "BCBUS5_57") (pintype "bidirectional"))
      (node (ref "U4") (pin "A6") (pinfunction "TDO_A6") (pintype "bidirectional"))
    )
    (net (code "28") (name "CPLD_TMS") (class "Default")
      (node (ref "U2") (pin "58") (pinfunction "BCBUS6_58") (pintype "bidirectional"))
      (node (ref "U4") (pin "K9") (pinfunction "TMS_K9") (pintype "bidirectional"))
    )
    (net (code "29") (name "DM") (class "Default")
      (node (ref "R4") (pin "1") (pinfunction "1_1") (pintype "passive"))
      (node (ref "U2") (pin "7") (pinfunction "DM_7") (pintype "bidirectional"))
    )
    (net (code "30") (name "DP") (class "Default")
      (node (ref "R5") (pin "1") (pinfunction "1_1") (pintype "passive"))
      (node (ref "U2") (pin "8") (pinfunction "DP_8") (pintype "bidirectional"))
    )
    (net (code "31") (name "ECLK") (class "Default")
      (node (ref "J7") (pin "1") (pinfunction "1_1") (pintype "passive"))
      (node (ref "U5") (pin "84") (pinfunction "ECLK_84") (pintype "bidirectional"))
    )
    (net (code "32") (name "FTDI_TCK") (class "Default")
      (node (ref "U2") (pin "16") (pinfunction "ADBUS0_16") (pintype "bidirectional"))
      (node (ref "U4") (pin "H10") (pinfunction "IO12_14_H10") (pintype "bidirectional"))
    )
    (net (code "33") (name "FTDI_TDI") (class "Default")
      (node (ref "Q1") (pin "3") (pinfunction "G_3") (pintype "passive"))
      (node (ref "R28") (pin "1") (pinfunction "1_1") (pintype "passive"))
      (node (ref "U2") (pin "17") (pinfunction "ADBUS1_17") (pintype "bidirectional"))
      (node (ref "U4") (pin "K8") (pinfunction "IO12_13_K8") (pintype "bidirectional"))
    )
    (net (code "34") (name "FTDI_TDO") (class "Default")
      (node (ref "U2") (pin "18") (pinfunction "ADBUS2_18") (pintype "bidirectional"))
      (node (ref "U4") (pin "H8") (pinfunction "IO12_12_H8") (pintype "bidirectional"))
    )
    (net (code "35") (name "FTDI_TMS") (class "Default")
      (node (ref "U2") (pin "19") (pinfunction "ADBUS3_19") (pintype "bidirectional"))
      (node (ref "U4") (pin "H5") (pinfunction "IO12_11_H5") (pintype "bidirectional"))
    )
    (net (code "36") (name "GIOA0") (class "Default")
      (node (ref "J2") (pin "3") (pinfunction "3_3") (pintype "passive"))
      (node (ref "U5") (pin "1") (pinfunction "GIOA0/SPI3CS3_1") (pintype "bidirectional"))
    )
    (net (code "37") (name "GIOA1") (class "Default")
      (node (ref "J2") (pin "4") (pinfunction "4_4") (pintype "passive"))
      (node (ref "U5") (pin "2") (pinfunction "GIOA1/SPI3CS2_2") (pintype "bidirectional"))
    )
    (net (code "38") (name "GIOA2") (class "Default")
      (node (ref "R47") (pin "2") (pinfunction "2_2") (pintype "passive"))
      (node (ref "U5") (pin "5") (pinfunction "GIOA2/SPI3CS1_5") (pintype "bidirectional"))
    )
    (net (code "39") (name "GIOA3") (class "Default")
      (node (ref "J10") (pin "18") (pinfunction "18_18") (pintype "passive"))
      (node (ref "U5") (pin "8") (pinfunction "GIOA3/SPI2CS3_8") (pintype "bidirectional"))
    )
    (net (code "40") (name "GIOA4") (class "Default")
      (node (ref "J2") (pin "10") (pinfunction "10_10") (pintype "passive"))
      (node (ref "U5") (pin "9") (pinfunction "GIOA4/SPI2CS2_9") (pintype "bidirectional"))
    )
    (net (code "41") (name "GIOA5") (class "Default")
      (node (ref "J6") (pin "1") (pinfunction "1_1") (pintype "passive"))
      (node (ref "U5") (pin "10") (pinfunction "GIOA5/EXTCLKIN_10") (pintype "bidirectional"))
    )
    (net (code "42") (name "GIOA6") (class "Default")
      (node (ref "J2") (pin "8") (pinfunction "8_8") (pintype "passive"))
      (node (ref "U5") (pin "12") (pinfunction "GIOA6/SPI2CS1/NHET31_12") (pintype "bidirectional"))
    )
    (net (code "43") (name "GIOA7") (class "Default")
      (node (ref "C46") (pin "1") (pinfunction "1_1") (pintype "passive"))
      (node (ref "J2") (pin "9") (pinfunction "9_9") (pintype "passive"))
      (node (ref "R35") (pin "2") (pinfunction "2_2") (pintype "passive"))
      (node (ref "S1") (pin "3") (pinfunction "3_3") (pintype "passive"))
      (node (ref "S1") (pin "4") (pinfunction "4_4") (pintype "passive"))
      (node (ref "U5") (pin "18") (pinfunction "GIOA7/NHET29_18") (pintype "bidirectional"))
    )
    (net (code "44") (name "GND") (class "Default")
      (node (ref "C1") (pin "2") (pinfunction "2_2") (pintype "passive"))
      (node (ref "C10") (pin "2") (pinfunction "2_2") (pintype "passive"))
      (node (ref "C11") (pin "2") (pinfunction "2_2") (pintype "passive"))
      (node (ref "C12") (pin "2") (pinfunction "2_2") (pintype "passive"))
      (node (ref "C13") (pin "2") (pinfunction "2_2") (pintype "passive"))
      (node (ref "C14") (pin "2") (pinfunction "2_2") (pintype "passive"))
      (node (ref "C15") (pin "2") (pinfunction "2_2") (pintype "passive"))
      (node (ref "C16") (pin "2") (pinfunction "2_2") (pintype "passive"))
      (node (ref "C17") (pin "2") (pinfunction "2_2") (pintype "passive"))
      (node (ref "C18") (pin "2") (pinfunction "2_2") (pintype "passive"))
      (node (ref "C19") (pin "2") (pinfunction "2_2") (pintype "passive"))
      (node (ref "C2") (pin "2") (pinfunction "2_2") (pintype "passive"))
      (node (ref "C20") (pin "2") (pinfunction "2_2") (pintype "passive"))
      (node (ref "C21") (pin "2") (pinfunction "2_2") (pintype "passive"))
      (node (ref "C22") (pin "2") (pinfunction "2_2") (pintype "passive"))
      (node (ref "C23") (pin "2") (pinfunction "2_2") (pintype "passive"))
      (node (ref "C24") (pin "2") (pinfunction "2_2") (pintype "passive"))
      (node (ref "C25") (pin "2") (pinfunction "2_2") (pintype "passive"))
      (node (ref "C26") (pin "2") (pinfunction "2_2") (pintype "passive"))
      (node (ref "C27") (pin "2") (pinfunction "2_2") (pintype "passive"))
      (node (ref "C28") (pin "2") (pinfunction "2_2") (pintype "passive"))
      (node (ref "C29") (pin "2") (pinfunction "2_2") (pintype "passive"))
      (node (ref "C3") (pin "-") (pinfunction "-_-") (pintype "passive"))
      (node (ref "C30") (pin "2") (pinfunction "2_2") (pintype "passive"))
      (node (ref "C31") (pin "2") (pinfunction "2_2") (pintype "passive"))
      (node (ref "C32") (pin "2") (pinfunction "2_2") (pintype "passive"))
      (node (ref "C33") (pin "2") (pinfunction "2_2") (pintype "passive"))
      (node (ref "C34") (pin "2") (pinfunction "2_2") (pintype "passive"))
      (node (ref "C35") (pin "2") (pinfunction "2_2") (pintype "passive"))
      (node (ref "C36") (pin "2") (pinfunction "2_2") (pintype "passive"))
      (node (ref "C37") (pin "2") (pinfunction "2_2") (pintype "passive"))
      (node (ref "C38") (pin "2") (pinfunction "2_2") (pintype "passive"))
      (node (ref "C39") (pin "2") (pinfunction "2_2") (pintype "passive"))
      (node (ref "C4") (pin "-") (pinfunction "-_-") (pintype "passive"))
      (node (ref "C40") (pin "2") (pinfunction "2_2") (pintype "passive"))
      (node (ref "C41") (pin "2") (pinfunction "2_2") (pintype "passive"))
      (node (ref "C42") (pin "2") (pinfunction "2_2") (pintype "passive"))
      (node (ref "C43") (pin "2") (pinfunction "2_2") (pintype "passive"))
      (node (ref "C44") (pin "2") (pinfunction "2_2") (pintype "passive"))
      (node (ref "C46") (pin "2") (pinfunction "2_2") (pintype "passive"))
      (node (ref "C47") (pin "2") (pinfunction "2_2") (pintype "passive"))
      (node (ref "C48") (pin "2") (pinfunction "2_2") (pintype "passive"))
      (node (ref "C5") (pin "2") (pinfunction "2_2") (pintype "passive"))
      (node (ref "C50") (pin "2") (pinfunction "2_2") (pintype "passive"))
      (node (ref "C51") (pin "2") (pinfunction "2_2") (pintype "passive"))
      (node (ref "C52") (pin "2") (pinfunction "2_2") (pintype "passive"))
      (node (ref "C53") (pin "2") (pinfunction "2_2") (pintype "passive"))
      (node (ref "C54") (pin "2") (pinfunction "2_2") (pintype "passive"))
      (node (ref "C55") (pin "2") (pinfunction "2_2") (pintype "passive"))
      (node (ref "C6") (pin "-") (pinfunction "-_-") (pintype "passive"))
      (node (ref "C9") (pin "2") (pinfunction "2_2") (pintype "passive"))
      (node (ref "D1") (pin "C") (pinfunction "C_C") (pintype "passive"))
      (node (ref "D11") (pin "C") (pinfunction "C_C") (pintype "passive"))
      (node (ref "D12") (pin "C") (pinfunction "C_C") (pintype "passive"))
      (node (ref "D2") (pin "1") (pinfunction "1_1") (pintype "passive"))
      (node (ref "D4") (pin "2") (pinfunction "2_2") (pintype "passive"))
      (node (ref "D8") (pin "C") (pinfunction "C_C") (pintype "passive"))
      (node (ref "J10") (pin "10") (pinfunction "10_10") (pintype "passive"))
      (node (ref "J10") (pin "19") (pinfunction "19_19") (pintype "passive"))
      (node (ref "J10") (pin "20") (pinfunction "20_20") (pintype "passive"))
      (node (ref "J10") (pin "29") (pinfunction "29_29") (pintype "passive"))
      (node (ref "J10") (pin "3") (pinfunction "3_3") (pintype "passive"))
      (node (ref "J10") (pin "30") (pinfunction "30_30") (pintype "passive"))
      (node (ref "J10") (pin "4") (pinfunction "4_4") (pintype "passive"))
      (node (ref "J10") (pin "9") (pinfunction "9_9") (pintype "passive"))
      (node (ref "J11") (pin "5") (pinfunction "5_5") (pintype "passive"))
      (node (ref "J12") (pin "10") (pinfunction "10_10") (pintype "passive"))
      (node (ref "J12") (pin "12") (pinfunction "12_12") (pintype "passive"))
      (node (ref "J12") (pin "4") (pinfunction "4_4") (pintype "passive"))
      (node (ref "J2") (pin "1") (pinfunction "1_1") (pintype "passive"))
      (node (ref "J3") (pin "2") (pinfunction "2_2") (pintype "passive"))
      (node (ref "J5") (pin "2") (pinfunction "2_2") (pintype "passive"))
      (node (ref "J5") (pin "3") (pinfunction "3_3") (pintype "passive"))
      (node (ref "JP1") (pin "1") (pinfunction "1_1") (pintype "passive"))
      (node (ref "R15") (pin "1") (pinfunction "1_1") (pintype "passive"))
      (node (ref "R31") (pin "1") (pinfunction "1_1") (pintype "passive"))
      (node (ref "R35") (pin "1") (pinfunction "1_1") (pintype "passive"))
      (node (ref "R42") (pin "2") (pinfunction "2_2") (pintype "passive"))
      (node (ref "R45") (pin "1") (pinfunction "1_1") (pintype "passive"))
      (node (ref "R7") (pin "2") (pinfunction "2_2") (pintype "passive"))
      (node (ref "S2") (pin "1") (pinfunction "1_1") (pintype "passive"))
      (node (ref "S2") (pin "2") (pinfunction "2_2") (pintype "passive"))
      (node (ref "S3") (pin "1") (pinfunction "1_1") (pintype "passive"))
      (node (ref "S3") (pin "2") (pinfunction "2_2") (pintype "passive"))
      (node (ref "TP14") (pin "1") (pinfunction "P$1_1") (pintype "bidirectional"))
      (node (ref "TP15") (pin "1") (pinfunction "P$1_1") (pintype "bidirectional"))
      (node (ref "TP16") (pin "1") (pinfunction "P$1_1") (pintype "bidirectional"))
      (node (ref "TP17") (pin "1") (pinfunction "P$1_1") (pintype "bidirectional"))
      (node (ref "TP4") (pin "1") (pinfunction "P$1_1") (pintype "bidirectional"))
      (node (ref "TP5") (pin "1") (pinfunction "P$1_1") (pintype "bidirectional"))
      (node (ref "TP6") (pin "1") (pinfunction "P$1_1") (pintype "bidirectional"))
      (node (ref "TP7") (pin "1") (pinfunction "P$1_1") (pintype "bidirectional"))
      (node (ref "U1") (pin "1") (pinfunction "GND1_1") (pintype "passive"))
      (node (ref "U1") (pin "12") (pinfunction "GND3_12") (pintype "passive"))
      (node (ref "U1") (pin "13") (pinfunction "GND4_13") (pintype "passive"))
      (node (ref "U1") (pin "24") (pinfunction "GND5_24") (pintype "passive"))
      (node (ref "U1") (pin "25") (pinfunction "P_GND_25") (pintype "bidirectional"))
      (node (ref "U1") (pin "6") (pinfunction "EN1_6") (pintype "input"))
      (node (ref "U1") (pin "7") (pinfunction "EN2_7") (pintype "input"))
      (node (ref "U1") (pin "9") (pinfunction "GND2_9") (pintype "passive"))
      (node (ref "U2") (pin "1") (pinfunction "GND1_1") (pintype "bidirectional"))
      (node (ref "U2") (pin "10") (pinfunction "GNDA_10") (pintype "bidirectional"))
      (node (ref "U2") (pin "11") (pinfunction "GND3_11") (pintype "bidirectional"))
      (node (ref "U2") (pin "13") (pinfunction "TEST_13") (pintype "bidirectional"))
      (node (ref "U2") (pin "15") (pinfunction "GND4_15") (pintype "bidirectional"))
      (node (ref "U2") (pin "25") (pinfunction "GND5_25") (pintype "bidirectional"))
      (node (ref "U2") (pin "35") (pinfunction "GND6_35") (pintype "bidirectional"))
      (node (ref "U2") (pin "47") (pinfunction "GND7_47") (pintype "bidirectional"))
      (node (ref "U2") (pin "5") (pinfunction "GND2_5") (pintype "bidirectional"))
      (node (ref "U2") (pin "51") (pinfunction "GND8_51") (pintype "bidirectional"))
      (node (ref "U3") (pin "5") (pinfunction "GND_5") (pintype "bidirectional"))
      (node (ref "U4") (pin "C7") (pinfunction "GND3_C7") (pintype "bidirectional"))
      (node (ref "U4") (pin "F8") (pinfunction "GND2_F8") (pintype "bidirectional"))
      (node (ref "U4") (pin "H4") (pinfunction "GND1_H4") (pintype "bidirectional"))
      (node (ref "U5") (pin "100") (pinfunction "VSS10_100") (pintype "bidirectional"))
      (node (ref "U5") (pin "17") (pinfunction "VSS2_17") (pintype "bidirectional"))
      (node (ref "U5") (pin "20") (pinfunction "VSS3_20") (pintype "bidirectional"))
      (node (ref "U5") (pin "29") (pinfunction "VSS4_29") (pintype "bidirectional"))
      (node (ref "U5") (pin "33") (pinfunction "VSS5_33") (pintype "bidirectional"))
      (node (ref "U5") (pin "47") (pinfunction "ADREFLO_47") (pintype "bidirectional"))
      (node (ref "U5") (pin "59") (pinfunction "VSS6_59") (pintype "bidirectional"))
      (node (ref "U5") (pin "7") (pinfunction "VSS1_7") (pintype "bidirectional"))
      (node (ref "U5") (pin "72") (pinfunction "VSS7_72") (pintype "bidirectional"))
      (node (ref "U5") (pin "86") (pinfunction "VSS8_86") (pintype "bidirectional"))
      (node (ref "U5") (pin "87") (pinfunction "VSS9_87") (pintype "bidirectional"))
      (node (ref "Y1") (pin "P$2") (pinfunction "P$2_P$2") (pintype "bidirectional"))
      (node (ref "Y1") (pin "P$4") (pinfunction "P$4_P$4") (pintype "bidirectional"))
    )
    (net (code "45") (name "GPIOH0") (class "Default")
      (node (ref "U2") (pin "26") (pinfunction "ACBUS0_26") (pintype "bidirectional"))
      (node (ref "U4") (pin "K1") (pinfunction "IO12_6_K1") (pintype "bidirectional"))
    )
    (net (code "46") (name "GPIOH1") (class "Default")
      (node (ref "U2") (pin "27") (pinfunction "ACBUS1_27") (pintype "bidirectional"))
      (node (ref "U4") (pin "J1") (pinfunction "IO12_5_J1") (pintype "bidirectional"))
    )
    (net (code "47") (name "GPIOH3") (class "Default")
      (node (ref "U2") (pin "29") (pinfunction "ACBUS3_29") (pintype "bidirectional"))
      (node (ref "U4") (pin "F3") (pinfunction "IO12_2_F3") (pintype "bidirectional"))
    )
    (net (code "48") (name "GPIOL0") (class "Default")
      (node (ref "U2") (pin "21") (pinfunction "ADBUS4_21") (pintype "bidirectional"))
      (node (ref "U4") (pin "K5") (pinfunction "IO12_10_K5") (pintype "bidirectional"))
    )
    (net (code "49") (name "GPIOL1") (class "Default")
      (node (ref "U2") (pin "22") (pinfunction "ADBUS5_22") (pintype "bidirectional"))
      (node (ref "U4") (pin "H3") (pinfunction "IO12_9_H3") (pintype "bidirectional"))
    )
    (net (code "50") (name "GPIOL2") (class "Default")
      (node (ref "U2") (pin "23") (pinfunction "ADBUS6_23") (pintype "bidirectional"))
      (node (ref "U4") (pin "K3") (pinfunction "IO12_8_K3") (pintype "bidirectional"))
    )
    (net (code "51") (name "GPIOL3") (class "Default")
      (node (ref "U2") (pin "24") (pinfunction "ADBUS7_24") (pintype "bidirectional"))
      (node (ref "U4") (pin "K2") (pinfunction "IO12_7_K2") (pintype "bidirectional"))
    )
    (net (code "52") (name "JTAG_SEL") (class "Default")
      (node (ref "C55") (pin "1") (pinfunction "1_1") (pintype "passive"))
      (node (ref "J12") (pin "8") (pinfunction "8_8") (pintype "passive"))
      (node (ref "Q3") (pin "3") (pinfunction "G_3") (pintype "passive"))
      (node (ref "R52") (pin "1") (pinfunction "1_1") (pintype "passive"))
    )
    (net (code "53") (name "MCU_RESET") (class "Default")
      (node (ref "C47") (pin "1") (pinfunction "1_1") (pintype "passive"))
      (node (ref "R33") (pin "1") (pinfunction "1_1") (pintype "passive"))
      (node (ref "R36") (pin "1") (pinfunction "1_1") (pintype "passive"))
      (node (ref "R39") (pin "1") (pinfunction "1_1") (pintype "passive"))
      (node (ref "U5") (pin "81") (pinfunction "RSTN_81") (pintype "bidirectional"))
    )
    (net (code "54") (name "MCU_RTCK") (class "Default")
      (node (ref "J12") (pin "9") (pinfunction "9_9") (pintype "passive"))
      (node (ref "R34") (pin "2") (pinfunction "2_2") (pintype "passive"))
      (node (ref "R56") (pin "1") (pinfunction "1_1") (pintype "passive"))
      (node (ref "U5") (pin "80") (pinfunction "RTCK_80") (pintype "bidirectional"))
    )
    (net (code "55") (name "MCU_TCK") (class "Default")
      (node (ref "J12") (pin "11") (pinfunction "11_11") (pintype "passive"))
      (node (ref "R32") (pin "1") (pinfunction "1_1") (pintype "passive"))
      (node (ref "R55") (pin "1") (pinfunction "1_1") (pintype "passive"))
      (node (ref "U5") (pin "79") (pinfunction "TCK_79") (pintype "bidirectional"))
    )
    (net (code "56") (name "MCU_TDI") (class "Default")
      (node (ref "J12") (pin "3") (pinfunction "3_3") (pintype "passive"))
      (node (ref "R27") (pin "1") (pinfunction "1_1") (pintype "passive"))
      (node (ref "R54") (pin "1") (pinfunction "1_1") (pintype "passive"))
      (node (ref "U5") (pin "77") (pinfunction "TDI_77") (pintype "bidirectional"))
    )
    (net (code "57") (name "MCU_TDO") (class "Default")
      (node (ref "J12") (pin "7") (pinfunction "7_7") (pintype "passive"))
      (node (ref "R30") (pin "1") (pinfunction "1_1") (pintype "passive"))
      (node (ref "U5") (pin "78") (pinfunction "TDO_78") (pintype "bidirectional"))
    )
    (net (code "58") (name "MCU_TMS") (class "Default")
      (node (ref "J12") (pin "1") (pinfunction "1_1") (pintype "passive"))
      (node (ref "R25") (pin "1") (pinfunction "1_1") (pintype "passive"))
      (node (ref "R53") (pin "1") (pinfunction "1_1") (pintype "passive"))
      (node (ref "U5") (pin "75") (pinfunction "TMS_75") (pintype "bidirectional"))
    )
    (net (code "59") (name "MCU_TRSTN") (class "Default")
      (node (ref "J12") (pin "2") (pinfunction "2_2") (pintype "passive"))
      (node (ref "R26") (pin "1") (pinfunction "1_1") (pintype "passive"))
      (node (ref "U5") (pin "76") (pinfunction "TRSTN_76") (pintype "bidirectional"))
    )
    (net (code "60") (name "NHET00") (class "Default")
      (node (ref "J4") (pin "1") (pinfunction "1_1") (pintype "passive"))
      (node (ref "U5") (pin "19") (pinfunction "NHET00_19") (pintype "bidirectional"))
    )
    (net (code "61") (name "NHET02") (class "Default")
      (node (ref "J4") (pin "2") (pinfunction "2_2") (pintype "passive"))
      (node (ref "U5") (pin "22") (pinfunction "NHET02_22") (pintype "bidirectional"))
    )
    (net (code "62") (name "NHET04") (class "Default")
      (node (ref "J4") (pin "3") (pinfunction "3_3") (pintype "passive"))
      (node (ref "U5") (pin "25") (pinfunction "NHET04_25") (pintype "bidirectional"))
    )
    (net (code "63") (name "NHET06") (class "Default")
      (node (ref "J4") (pin "4") (pinfunction "4_4") (pintype "passive"))
      (node (ref "U5") (pin "26") (pinfunction "NHET06_26") (pintype "bidirectional"))
    )
    (net (code "64") (name "NHET08") (class "Default")
      (node (ref "R48") (pin "2") (pinfunction "2_2") (pintype "passive"))
      (node (ref "U5") (pin "74") (pinfunction "NHET08_74") (pintype "bidirectional"))
    )
    (net (code "65") (name "NHET10") (class "Default")
      (node (ref "J4") (pin "5") (pinfunction "5_5") (pintype "passive"))
      (node (ref "U5") (pin "83") (pinfunction "NHET10_83") (pintype "bidirectional"))
    )
    (net (code "66") (name "NHET12") (class "Default")
      (node (ref "J4") (pin "6") (pinfunction "6_6") (pintype "passive"))
      (node (ref "U5") (pin "89") (pinfunction "NHET12_89") (pintype "bidirectional"))
    )
    (net (code "67") (name "NHET14") (class "Default")
      (node (ref "J4") (pin "7") (pinfunction "7_7") (pintype "passive"))
      (node (ref "U5") (pin "90") (pinfunction "NHET14_90") (pintype "bidirectional"))
    )
    (net (code "68") (name "NHET16") (class "Default")
      (node (ref "J4") (pin "8") (pinfunction "8_8") (pintype "passive"))
      (node (ref "U5") (pin "97") (pinfunction "NHET16_97") (pintype "bidirectional"))
    )
    (net (code "69") (name "NHET18") (class "Default")
      (node (ref "J4") (pin "9") (pinfunction "9_9") (pintype "passive"))
      (node (ref "U5") (pin "98") (pinfunction "NHET18_98") (pintype "bidirectional"))
    )
    (net (code "70") (name "NHET22") (class "Default")
      (node (ref "J4") (pin "10") (pinfunction "10_10") (pintype "passive"))
      (node (ref "U5") (pin "11") (pinfunction "NHET22_11") (pintype "bidirectional"))
    )
    (net (code "71") (name "NHET24") (class "Default")
      (node (ref "J2") (pin "2") (pinfunction "2_2") (pintype "passive"))
      (node (ref "U5") (pin "64") (pinfunction "NHET24_64") (pintype "bidirectional"))
    )
    (net (code "72") (name "Net-(D1-PadA)") (class "Default")
      (node (ref "D1") (pin "A") (pinfunction "A_A") (pintype "passive"))
      (node (ref "R3") (pin "1") (pinfunction "1_1") (pintype "passive"))
    )
    (net (code "73") (name "Net-(D2-Pad2)") (class "Default")
      (node (ref "D2") (pin "2") (pinfunction "2_2") (pintype "passive"))
      (node (ref "J11") (pin "2") (pinfunction "2_2") (pintype "passive"))
      (node (ref "R4") (pin "2") (pinfunction "2_2") (pintype "passive"))
    )
    (net (code "74") (name "Net-(D4-Pad1)") (class "Default")
      (node (ref "D4") (pin "1") (pinfunction "1_1") (pintype "passive"))
      (node (ref "J11") (pin "3") (pinfunction "3_3") (pintype "passive"))
      (node (ref "R5") (pin "2") (pinfunction "2_2") (pintype "passive"))
    )
    (net (code "75") (name "Net-(D5-PadC)") (class "Default")
      (node (ref "D5") (pin "C") (pinfunction "C_C") (pintype "passive"))
      (node (ref "R16") (pin "2") (pinfunction "2_2") (pintype "passive"))
    )
    (net (code "76") (name "Net-(D6-PadC)") (class "Default")
      (node (ref "D6") (pin "C") (pinfunction "C_C") (pintype "passive"))
      (node (ref "R17") (pin "2") (pinfunction "2_2") (pintype "passive"))
    )
    (net (code "77") (name "Net-(D7-PadA)") (class "Default")
      (node (ref "D7") (pin "A") (pinfunction "A_A") (pintype "passive"))
      (node (ref "R19") (pin "2") (pinfunction "2_2") (pintype "passive"))
    )
    (net (code "78") (name "Net-(D8-PadA)") (class "Default")
      (node (ref "D8") (pin "A") (pinfunction "A_A") (pintype "passive"))
      (node (ref "R49") (pin "1") (pinfunction "1_1") (pintype "passive"))
    )
    (net (code "79") (name "Net-(D10-PadA)") (class "Default")
      (node (ref "D10") (pin "A") (pinfunction "A_A") (pintype "passive"))
      (node (ref "R40") (pin "1") (pinfunction "1_1") (pintype "passive"))
    )
    (net (code "80") (name "Net-(D11-PadA)") (class "Default")
      (node (ref "D11") (pin "A") (pinfunction "A_A") (pintype "passive"))
      (node (ref "R48") (pin "1") (pinfunction "1_1") (pintype "passive"))
    )
    (net (code "81") (name "Net-(D12-PadA)") (class "Default")
      (node (ref "D12") (pin "A") (pinfunction "A_A") (pintype "passive"))
      (node (ref "R47") (pin "1") (pinfunction "1_1") (pintype "passive"))
    )
    (net (code "82") (name "Net-(F1-Pad1)") (class "Default")
      (node (ref "F1") (pin "1") (pinfunction "1_1") (pintype "passive"))
      (node (ref "J11") (pin "1") (pinfunction "1_1") (pintype "passive"))
    )
    (net (code "83") (name "Net-(J1-Pad3)") (class "Default")
      (node (ref "J1") (pin "3") (pinfunction "3_3") (pintype "passive"))
      (node (ref "R44") (pin "1") (pinfunction "1_1") (pintype "passive"))
    )
    (net (code "84") (name "Net-(J1-Pad4)") (class "Default")
      (node (ref "J1") (pin "4") (pinfunction "4_4") (pintype "passive"))
      (node (ref "R46") (pin "1") (pinfunction "1_1") (pintype "passive"))
    )
    (net (code "85") (name "Net-(J1-Pad5)") (class "Default")
      (node (ref "J1") (pin "5") (pinfunction "5_5") (pintype "passive"))
      (node (ref "J6") (pin "2") (pinfunction "2_2") (pintype "passive"))
    )
    (net (code "86") (name "Net-(J1-Pad6)") (class "Default")
      (node (ref "J1") (pin "6") (pinfunction "6_6") (pintype "passive"))
      (node (ref "J7") (pin "2") (pinfunction "2_2") (pintype "passive"))
    )
    (net (code "87") (name "Net-(J2-Pad6)") (class "Default")
      (node (ref "J2") (pin "6") (pinfunction "6_6") (pintype "passive"))
      (node (ref "J9") (pin "2") (pinfunction "2_2") (pintype "passive"))
    )
    (net (code "88") (name "Net-(J2-Pad7)") (class "Default")
      (node (ref "J2") (pin "7") (pinfunction "7_7") (pintype "passive"))
      (node (ref "J8") (pin "2") (pinfunction "2_2") (pintype "passive"))
    )
    (net (code "89") (name "Net-(J11-P$1)") (class "Default")
      (node (ref "J11") (pin "10") (pinfunction "P$1_10") (pintype "bidirectional"))
      (node (ref "J11") (pin "11") (pinfunction "P$2_11") (pintype "bidirectional"))
      (node (ref "J11") (pin "6") (pinfunction "6_6") (pintype "bidirectional"))
      (node (ref "J11") (pin "7") (pinfunction "7_7") (pintype "bidirectional"))
      (node (ref "J11") (pin "8") (pinfunction "8_8") (pintype "bidirectional"))
      (node (ref "J11") (pin "9") (pinfunction "9_9") (pintype "bidirectional"))
      (node (ref "R7") (pin "1") (pinfunction "1_1") (pintype "passive"))
    )
    (net (code "90") (name "Net-(J12-Pad13)") (class "Default")
      (node (ref "J12") (pin "13") (pinfunction "13_13") (pintype "passive"))
      (node (ref "R50") (pin "1") (pinfunction "1_1") (pintype "passive"))
    )
    (net (code "91") (name "Net-(J12-Pad14)") (class "Default")
      (node (ref "J12") (pin "14") (pinfunction "14_14") (pintype "passive"))
      (node (ref "R51") (pin "1") (pinfunction "1_1") (pintype "passive"))
    )
    (net (code "92") (name "Net-(JP1-Pad2)") (class "Default")
      (node (ref "JP1") (pin "2") (pinfunction "2_2") (pintype "passive"))
      (node (ref "R43") (pin "2") (pinfunction "2_2") (pintype "passive"))
    )
    (net (code "93") (name "Net-(Q1-D)") (class "Default")
      (node (ref "Q1") (pin "1") (pinfunction "D_1") (pintype "passive"))
      (node (ref "R49") (pin "2") (pinfunction "2_2") (pintype "passive"))
    )
    (net (code "94") (name "Net-(R38-Pad2)") (class "Default")
      (node (ref "R38") (pin "2") (pinfunction "2_2") (pintype "passive"))
      (node (ref "S1") (pin "1") (pinfunction "1_1") (pintype "passive"))
      (node (ref "S1") (pin "2") (pinfunction "2_2") (pintype "passive"))
    )
    (net (code "95") (name "Net-(R39-Pad2)") (class "Default")
      (node (ref "R39") (pin "2") (pinfunction "2_2") (pintype "passive"))
      (node (ref "S2") (pin "3") (pinfunction "3_3") (pintype "passive"))
      (node (ref "S2") (pin "4") (pinfunction "4_4") (pintype "passive"))
    )
    (net (code "96") (name "Net-(R41-Pad2)") (class "Default")
      (node (ref "R41") (pin "2") (pinfunction "2_2") (pintype "passive"))
      (node (ref "S3") (pin "3") (pinfunction "3_3") (pintype "passive"))
      (node (ref "S3") (pin "4") (pinfunction "4_4") (pintype "passive"))
    )
    (net (code "97") (name "Net-(U1-MR)") (class "Default")
      (node (ref "R1") (pin "1") (pinfunction "1_1") (pintype "passive"))
      (node (ref "R2") (pin "1") (pinfunction "1_1") (pintype "passive"))
      (node (ref "U1") (pin "18") (pinfunction "PG2_18") (pintype "output"))
      (node (ref "U1") (pin "19") (pinfunction "PG1_19") (pintype "output"))
      (node (ref "U1") (pin "5") (pinfunction "MR_5") (pintype "input"))
    )
    (net (code "98") (name "Net-(U1-RESET)") (class "Default")
      (node (ref "D3") (pin "C") (pinfunction "C_C") (pintype "passive"))
      (node (ref "R6") (pin "1") (pinfunction "1_1") (pintype "passive"))
      (node (ref "U1") (pin "8") (pinfunction "RESET_8") (pintype "output"))
    )
    (net (code "99") (name "Net-(U2-BCBUS3)") (class "Default")
      (node (ref "R16") (pin "1") (pinfunction "1_1") (pintype "passive"))
      (node (ref "U2") (pin "54") (pinfunction "BCBUS3_54") (pintype "bidirectional"))
    )
    (net (code "100") (name "Net-(U2-BCBUS4)") (class "Default")
      (node (ref "R17") (pin "1") (pinfunction "1_1") (pintype "passive"))
      (node (ref "U2") (pin "55") (pinfunction "BCBUS4_55") (pintype "bidirectional"))
    )
    (net (code "101") (name "Net-(U2-BDBUS0)") (class "Default")
      (node (ref "R8") (pin "1") (pinfunction "1_1") (pintype "passive"))
      (node (ref "U2") (pin "38") (pinfunction "BDBUS0_38") (pintype "bidirectional"))
    )
    (net (code "102") (name "Net-(U2-BDBUS1)") (class "Default")
      (node (ref "R9") (pin "1") (pinfunction "1_1") (pintype "passive"))
      (node (ref "U2") (pin "39") (pinfunction "BDBUS1_39") (pintype "bidirectional"))
    )
    (net (code "103") (name "Net-(U2-BDBUS2)") (class "Default")
      (node (ref "R10") (pin "2") (pinfunction "2_2") (pintype "passive"))
      (node (ref "U2") (pin "40") (pinfunction "BDBUS2_40") (pintype "bidirectional"))
    )
    (net (code "104") (name "Net-(U2-BDBUS3)") (class "Default")
      (node (ref "R10") (pin "1") (pinfunction "1_1") (pintype "passive"))
      (node (ref "U2") (pin "41") (pinfunction "BDBUS3_41") (pintype "bidirectional"))
    )
    (net (code "105") (name "Net-(U2-EECLK)") (class "Default")
      (node (ref "R13") (pin "1") (pinfunction "1_1") (pintype "passive"))
      (node (ref "U2") (pin "62") (pinfunction "EECLK_62") (pintype "bidirectional"))
      (node (ref "U3") (pin "2") (pinfunction "SK_2") (pintype "bidirectional"))
    )
    (net (code "106") (name "Net-(U2-EECS)") (class "Default")
      (node (ref "R12") (pin "1") (pinfunction "1_1") (pintype "passive"))
      (node (ref "U2") (pin "63") (pinfunction "EECS_63") (pintype "bidirectional"))
      (node (ref "U3") (pin "1") (pinfunction "CS_1") (pintype "bidirectional"))
    )
    (net (code "107") (name "Net-(U2-EEDATA)") (class "Default")
      (node (ref "R18") (pin "2") (pinfunction "2_2") (pintype "passive"))
      (node (ref "U2") (pin "61") (pinfunction "EEDATA_61") (pintype "bidirectional"))
      (node (ref "U3") (pin "3") (pinfunction "DIN_3") (pintype "bidirectional"))
    )
    (net (code "108") (name "Net-(U2-OSCI)") (class "Default")
      (node (ref "C24") (pin "1") (pinfunction "1_1") (pintype "passive"))
      (node (ref "U2") (pin "2") (pinfunction "OSCI_2") (pintype "bidirectional"))
      (node (ref "Y1") (pin "P$3") (pinfunction "P$3_P$3") (pintype "bidirectional"))
    )
    (net (code "109") (name "Net-(U2-OSCO)") (class "Default")
      (node (ref "C25") (pin "1") (pinfunction "1_1") (pintype "passive"))
      (node (ref "U2") (pin "3") (pinfunction "OSCO_3") (pintype "bidirectional"))
      (node (ref "Y1") (pin "P$1") (pinfunction "P$1_P$1") (pintype "bidirectional"))
    )
    (net (code "110") (name "Net-(U2-REF)") (class "Default")
      (node (ref "R15") (pin "2") (pinfunction "2_2") (pintype "passive"))
      (node (ref "U2") (pin "6") (pinfunction "REF_6") (pintype "bidirectional"))
    )
    (net (code "111") (name "Net-(U2-RESET)") (class "Default")
      (node (ref "R11") (pin "2") (pinfunction "2_2") (pintype "passive"))
      (node (ref "U2") (pin "14") (pinfunction "RESET_14") (pintype "bidirectional"))
    )
    (net (code "112") (name "Net-(U2-VPHY)") (class "Default")
      (node (ref "C21") (pin "1") (pinfunction "1_1") (pintype "passive"))
      (node (ref "C22") (pin "1") (pinfunction "1_1") (pintype "passive"))
      (node (ref "FB2") (pin "2") (pinfunction "2_2") (pintype "passive"))
      (node (ref "U2") (pin "4") (pinfunction "VPHY_4") (pintype "bidirectional"))
    )
    (net (code "113") (name "Net-(U2-VPLL)") (class "Default")
      (node (ref "C19") (pin "1") (pinfunction "1_1") (pintype "passive"))
      (node (ref "C20") (pin "1") (pinfunction "1_1") (pintype "passive"))
      (node (ref "FB1") (pin "2") (pinfunction "2_2") (pintype "passive"))
      (node (ref "U2") (pin "9") (pinfunction "VPLL_9") (pintype "bidirectional"))
    )
    (net (code "114") (name "Net-(U3-DOUT)") (class "Default")
      (node (ref "R14") (pin "1") (pinfunction "1_1") (pintype "passive"))
      (node (ref "R18") (pin "1") (pinfunction "1_1") (pintype "passive"))
      (node (ref "U3") (pin "4") (pinfunction "DOUT_4") (pintype "bidirectional"))
    )
    (net (code "115") (name "Net-(U4-I)") (class "Default")
      (node (ref "R34") (pin "1") (pinfunction "1_1") (pintype "passive"))
      (node (ref "U4") (pin "D10") (pinfunction "I_D10") (pintype "bidirectional"))
    )
    (net (code "116") (name "Net-(U4-IO21_5)") (class "Default")
      (node (ref "R25") (pin "2") (pinfunction "2_2") (pintype "passive"))
      (node (ref "U4") (pin "A3") (pinfunction "IO21_6_A3") (pintype "bidirectional"))
      (node (ref "U4") (pin "C1") (pinfunction "IO21_5_C1") (pintype "bidirectional"))
    )
    (net (code "117") (name "Net-(U4-IO21_7)") (class "Default")
      (node (ref "R26") (pin "2") (pinfunction "2_2") (pintype "passive"))
      (node (ref "U4") (pin "A2") (pinfunction "IO21_7_A2") (pintype "bidirectional"))
    )
    (net (code "118") (name "Net-(U4-IO21_8)") (class "Default")
      (node (ref "R27") (pin "2") (pinfunction "2_2") (pintype "passive"))
      (node (ref "U4") (pin "B1") (pinfunction "IO21_8_B1") (pintype "bidirectional"))
    )
    (net (code "119") (name "Net-(U4-IO21_9)") (class "Default")
      (node (ref "R29") (pin "2") (pinfunction "2_2") (pintype "passive"))
      (node (ref "U4") (pin "A1") (pinfunction "IO21_9_A1") (pintype "bidirectional"))
    )
    (net (code "120") (name "Net-(U4-IO21_10)") (class "Default")
      (node (ref "R30") (pin "2") (pinfunction "2_2") (pintype "passive"))
      (node (ref "U4") (pin "C4") (pinfunction "IO21_10_C4") (pintype "bidirectional"))
    )
    (net (code "121") (name "Net-(U4-IO21_11)") (class "Default")
      (node (ref "R32") (pin "2") (pinfunction "2_2") (pintype "passive"))
      (node (ref "U4") (pin "A10") (pinfunction "IO21_13_A10") (pintype "bidirectional"))
      (node (ref "U4") (pin "C5") (pinfunction "IO21_11_C5") (pintype "bidirectional"))
      (node (ref "U4") (pin "C8") (pinfunction "IO21_12_C8") (pintype "bidirectional"))
    )
    (net (code "122") (name "Net-(U4-IO21_14)") (class "Default")
      (node (ref "R33") (pin "2") (pinfunction "2_2") (pintype "passive"))
      (node (ref "U4") (pin "B10") (pinfunction "IO21_14_B10") (pintype "bidirectional"))
    )
    (net (code "123") (name "Net-(U5A-KELVIN_GND)") (class "Default")
      (node (ref "C45") (pin "2") (pinfunction "2_2") (pintype "passive"))
      (node (ref "C49") (pin "1") (pinfunction "1_1") (pintype "passive"))
      (node (ref "U5") (pin "15") (pinfunction "KELVIN_GND_15") (pintype "bidirectional"))
    )
    (net (code "124") (name "Net-(U5A-NERROR)") (class "Default")
      (node (ref "D10") (pin "C") (pinfunction "C_C") (pintype "passive"))
      (node (ref "U5") (pin "82") (pinfunction "NERROR_82") (pintype "bidirectional"))
    )
    (net (code "125") (name "Net-(U5A-OSCIN)") (class "Default")
      (node (ref "C49") (pin "2") (pinfunction "2_2") (pintype "passive"))
      (node (ref "R43") (pin "1") (pinfunction "1_1") (pintype "passive"))
      (node (ref "U5") (pin "14") (pinfunction "OSCIN_14") (pintype "bidirectional"))
      (node (ref "Y2") (pin "P$3") (pinfunction "P$3_P$3") (pintype "bidirectional"))
    )
    (net (code "126") (name "Net-(U5A-OSCOUT)") (class "Default")
      (node (ref "C45") (pin "1") (pinfunction "1_1") (pintype "passive"))
      (node (ref "U5") (pin "16") (pinfunction "OSCOUT_16") (pintype "bidirectional"))
      (node (ref "Y2") (pin "P$1") (pinfunction "P$1_P$1") (pintype "bidirectional"))
    )
    (net (code "127") (name "Net-(U5A-TEST)") (class "Default")
      (node (ref "R42") (pin "1") (pinfunction "1_1") (pintype "passive"))
      (node (ref "U5") (pin "24") (pinfunction "TEST_24") (pintype "bidirectional"))
    )
    (net (code "128") (name "Net-(U5B-ADREFHI)") (class "Default")
      (node (ref "C52") (pin "1") (pinfunction "1_1") (pintype "passive"))
      (node (ref "C53") (pin "1") (pinfunction "1_1") (pintype "passive"))
      (node (ref "FB3") (pin "2") (pinfunction "2_2") (pintype "passive"))
      (node (ref "U5") (pin "46") (pinfunction "ADREFHI_46") (pintype "bidirectional"))
    )
    (net (code "129") (name "POR_NRESET") (class "Default")
      (node (ref "C48") (pin "1") (pinfunction "1_1") (pintype "passive"))
      (node (ref "D3") (pin "A") (pinfunction "A_A") (pintype "passive"))
      (node (ref "J2") (pin "5") (pinfunction "5_5") (pintype "passive"))
      (node (ref "R37") (pin "1") (pinfunction "1_1") (pintype "passive"))
      (node (ref "R41") (pin "1") (pinfunction "1_1") (pintype "passive"))
      (node (ref "TP3") (pin "1") (pinfunction "P$1_1") (pintype "bidirectional"))
      (node (ref "U5") (pin "31") (pinfunction "PORRSTN_31") (pintype "bidirectional"))
    )
    (net (code "130") (name "POWERGOOD") (class "Default")
      (node (ref "C30") (pin "1") (pinfunction "1_1") (pintype "passive"))
      (node (ref "R20") (pin "1") (pinfunction "1_1") (pintype "passive"))
      (node (ref "U4") (pin "F10") (pinfunction "IO12_16_F10") (pintype "bidirectional"))
    )
    (net (code "131") (name "POWER_EN") (class "Default")
      (node (ref "D7") (pin "C") (pinfunction "C_C") (pintype "passive"))
      (node (ref "U2") (pin "60") (pinfunction "PWREN_60") (pintype "bidirectional"))
      (node (ref "U4") (pin "G3") (pinfunction "IO12_4_G3") (pintype "bidirectional"))
    )
    (net (code "132") (name "PWR_DET") (class "Default")
      (node (ref "U2") (pin "28") (pinfunction "ACBUS2_28") (pintype "bidirectional"))
      (node (ref "U4") (pin "H1") (pinfunction "IO12_3_H1") (pintype "bidirectional"))
    )
    (net (code "133") (name "SCI1_RX") (class "Default")
      (node (ref "R44") (pin "2") (pinfunction "2_2") (pintype "passive"))
      (node (ref "R8") (pin "2") (pinfunction "2_2") (pintype "passive"))
      (node (ref "U5") (pin "94") (pinfunction "LIN1RX_SCI1RX_94") (pintype "bidirectional"))
    )
    (net (code "134") (name "SCI1_TX") (class "Default")
      (node (ref "R46") (pin "2") (pinfunction "2_2") (pintype "passive"))
      (node (ref "R9") (pin "2") (pinfunction "2_2") (pintype "passive"))
      (node (ref "U5") (pin "95") (pinfunction "LIN1TX_SCI1TX_95") (pintype "bidirectional"))
    )
    (net (code "135") (name "SPARE0") (class "Default")
      (node (ref "R21") (pin "2") (pinfunction "2_2") (pintype "passive"))
      (node (ref "U2") (pin "30") (pinfunction "ACBUS4_30") (pintype "bidirectional"))
      (node (ref "U4") (pin "F1") (pinfunction "IO21_1_F1") (pintype "bidirectional"))
    )
    (net (code "136") (name "SPARE1") (class "Default")
      (node (ref "R22") (pin "2") (pinfunction "2_2") (pintype "passive"))
      (node (ref "U2") (pin "32") (pinfunction "ACBUS5_32") (pintype "bidirectional"))
      (node (ref "U4") (pin "E3") (pinfunction "IO21_2_E3") (pintype "bidirectional"))
    )
    (net (code "137") (name "SPARE2") (class "Default")
      (node (ref "R23") (pin "2") (pinfunction "2_2") (pintype "passive"))
      (node (ref "U2") (pin "33") (pinfunction "ACBUS6_33") (pintype "bidirectional"))
      (node (ref "U4") (pin "E1") (pinfunction "IO21_3_E1") (pintype "bidirectional"))
    )
    (net (code "138") (name "SPARE3") (class "Default")
      (node (ref "R24") (pin "2") (pinfunction "2_2") (pintype "passive"))
      (node (ref "U2") (pin "34") (pinfunction "ACBUS7_34") (pintype "bidirectional"))
      (node (ref "U4") (pin "D1") (pinfunction "IO21_4_D1") (pintype "bidirectional"))
    )
    (net (code "139") (name "SPI1CLK") (class "Default")
      (node (ref "J1") (pin "7") (pinfunction "7_7") (pintype "passive"))
      (node (ref "U5") (pin "67") (pinfunction "SPI1CLK_67") (pintype "bidirectional"))
    )
    (net (code "140") (name "SPI1CS0") (class "Default")
      (node (ref "J10") (pin "16") (pinfunction "16_16") (pintype "passive"))
      (node (ref "U5") (pin "73") (pinfunction "SPI1CS0_73") (pintype "bidirectional"))
    )
    (net (code "141") (name "SPI1CS1") (class "Default")
      (node (ref "J1") (pin "8") (pinfunction "8_8") (pintype "passive"))
      (node (ref "J10") (pin "17") (pinfunction "17_17") (pintype "passive"))
      (node (ref "U5") (pin "93") (pinfunction "SPI1CS1/EQEPS_93") (pintype "bidirectional"))
    )
    (net (code "142") (name "SPI1CS2") (class "Default")
      (node (ref "J1") (pin "9") (pinfunction "9_9") (pintype "passive"))
      (node (ref "U5") (pin "27") (pinfunction "SPI1CS2_27") (pintype "bidirectional"))
    )
    (net (code "143") (name "SPI1CS3") (class "Default")
      (node (ref "J1") (pin "10") (pinfunction "10_10") (pintype "passive"))
      (node (ref "U5") (pin "39") (pinfunction "SPI1CS3/NHET26_39") (pintype "bidirectional"))
    )
    (net (code "144") (name "SPI1ENA") (class "Default")
      (node (ref "J8") (pin "3") (pinfunction "3_3") (pintype "passive"))
      (node (ref "U5") (pin "68") (pinfunction "SPI1ENA/NHET30_68") (pintype "bidirectional"))
    )
    (net (code "145") (name "SPI1SIMO") (class "Default")
      (node (ref "J9") (pin "1") (pinfunction "1_1") (pintype "passive"))
      (node (ref "U5") (pin "65") (pinfunction "SPI1SIMO_65") (pintype "bidirectional"))
    )
    (net (code "146") (name "SPI1SOMI") (class "Default")
      (node (ref "J8") (pin "1") (pinfunction "1_1") (pintype "passive"))
      (node (ref "U5") (pin "66") (pinfunction "SPI1SOMI_66") (pintype "bidirectional"))
    )
    (net (code "147") (name "SPI2CLK") (class "Default")
      (node (ref "J10") (pin "24") (pinfunction "24_24") (pintype "passive"))
      (node (ref "U5") (pin "71") (pinfunction "SPI2CLK_71") (pintype "bidirectional"))
    )
    (net (code "148") (name "SPI2CS0") (class "Default")
      (node (ref "J10") (pin "21") (pinfunction "21_21") (pintype "passive"))
      (node (ref "U5") (pin "23") (pinfunction "SPI2CS0_23") (pintype "bidirectional"))
    )
    (net (code "149") (name "SPI2SIMO") (class "Default")
      (node (ref "J10") (pin "23") (pinfunction "23_23") (pintype "passive"))
      (node (ref "U5") (pin "70") (pinfunction "SPI2SIMO_70") (pintype "bidirectional"))
    )
    (net (code "150") (name "SPI2SOMI") (class "Default")
      (node (ref "J10") (pin "22") (pinfunction "22_22") (pintype "passive"))
      (node (ref "U5") (pin "69") (pinfunction "SPI2SOMI_69") (pintype "bidirectional"))
    )
    (net (code "151") (name "SPI3CLK") (class "Default")
      (node (ref "J10") (pin "11") (pinfunction "11_11") (pintype "passive"))
      (node (ref "U5") (pin "36") (pinfunction "SPI3CLK/EQEPA_36") (pintype "bidirectional"))
    )
    (net (code "152") (name "SPI3CS0") (class "Default")
      (node (ref "J10") (pin "13") (pinfunction "13_13") (pintype "passive"))
      (node (ref "U5") (pin "38") (pinfunction "SPI3CS0/EQEPI_38") (pintype "bidirectional"))
    )
    (net (code "153") (name "SPI3ENA") (class "Default")
      (node (ref "J10") (pin "15") (pinfunction "15_15") (pintype "passive"))
      (node (ref "U5") (pin "37") (pinfunction "SPI3ENA/EQEPB_37") (pintype "bidirectional"))
    )
    (net (code "154") (name "SPI3SIMO") (class "Default")
      (node (ref "J10") (pin "14") (pinfunction "14_14") (pintype "passive"))
      (node (ref "U5") (pin "35") (pinfunction "SPI3SIMO_35") (pintype "bidirectional"))
    )
    (net (code "155") (name "SPI3SOMI") (class "Default")
      (node (ref "J10") (pin "12") (pinfunction "12_12") (pintype "passive"))
      (node (ref "U5") (pin "34") (pinfunction "SPI3SOMI_34") (pintype "bidirectional"))
    )
    (net (code "156") (name "SUSPEED") (class "Default")
      (node (ref "U2") (pin "36") (pinfunction "SUSPEED_36") (pintype "bidirectional"))
      (node (ref "U4") (pin "G1") (pinfunction "IO12_1_G1") (pintype "bidirectional"))
    )
    (net (code "157") (name "T_DIS") (class "Default")
      (node (ref "Q3") (pin "1") (pinfunction "D_1") (pintype "passive"))
      (node (ref "R29") (pin "1") (pinfunction "1_1") (pintype "passive"))
      (node (ref "R31") (pin "2") (pinfunction "2_2") (pintype "passive"))
    )
    (net (code "158") (name "VCC") (class "Default")
      (node (ref "C31") (pin "1") (pinfunction "1_1") (pintype "passive"))
      (node (ref "C32") (pin "1") (pinfunction "1_1") (pintype "passive"))
      (node (ref "C33") (pin "1") (pinfunction "1_1") (pintype "passive"))
      (node (ref "C34") (pin "1") (pinfunction "1_1") (pintype "passive"))
      (node (ref "C35") (pin "1") (pinfunction "1_1") (pintype "passive"))
      (node (ref "C36") (pin "1") (pinfunction "1_1") (pintype "passive"))
      (node (ref "C37") (pin "1") (pinfunction "1_1") (pintype "passive"))
      (node (ref "C38") (pin "1") (pinfunction "1_1") (pintype "passive"))
      (node (ref "C6") (pin "+") (pinfunction "+_+") (pintype "passive"))
      (node (ref "TP2") (pin "1") (pinfunction "P$1_1") (pintype "bidirectional"))
      (node (ref "U1") (pin "14") (pinfunction "VOUT2_A_14") (pintype "passive"))
      (node (ref "U1") (pin "15") (pinfunction "VOUT2_B_15") (pintype "passive"))
      (node (ref "U1") (pin "16") (pinfunction "VSENSE2_16") (pintype "input"))
      (node (ref "U5") (pin "13") (pinfunction "VCC1_13") (pintype "bidirectional"))
      (node (ref "U5") (pin "21") (pinfunction "VCC2_21") (pintype "bidirectional"))
      (node (ref "U5") (pin "30") (pinfunction "VCC_SRAM_30") (pintype "bidirectional"))
      (node (ref "U5") (pin "32") (pinfunction "VNMA_32") (pintype "bidirectional"))
      (node (ref "U5") (pin "61") (pinfunction "VCC4_61") (pintype "bidirectional"))
      (node (ref "U5") (pin "88") (pinfunction "VCC5_88") (pintype "bidirectional"))
      (node (ref "U5") (pin "99") (pinfunction "VCC3_99") (pintype "bidirectional"))
    )
    (net (code "159") (name "unconnected-(J11-Pad4)") (class "Default")
      (node (ref "J11") (pin "4") (pinfunction "4_4") (pintype "passive"))
    )
    (net (code "160") (name "unconnected-(J12-Pad6)") (class "Default")
      (node (ref "J12") (pin "6") (pinfunction "6_6") (pintype "passive"))
    )
    (net (code "161") (name "unconnected-(U1-NC1-Pad4)") (class "Default")
      (node (ref "U1") (pin "4") (pinfunction "NC1_4") (pintype "bidirectional"))
    )
    (net (code "162") (name "unconnected-(U1-NC2-Pad17)") (class "Default")
      (node (ref "U1") (pin "17") (pinfunction "NC2_17") (pintype "bidirectional"))
    )
    (net (code "163") (name "unconnected-(U1-NC3-Pad20)") (class "Default")
      (node (ref "U1") (pin "20") (pinfunction "NC3_20") (pintype "bidirectional"))
    )
    (net (code "164") (name "unconnected-(U2-BCBUS0-Pad48)") (class "Default")
      (node (ref "U2") (pin "48") (pinfunction "BCBUS0_48") (pintype "bidirectional"))
    )
    (net (code "165") (name "unconnected-(U2-BCBUS7-Pad59)") (class "Default")
      (node (ref "U2") (pin "59") (pinfunction "BCBUS7_59") (pintype "bidirectional"))
    )
    (net (code "166") (name "unconnected-(U2-BDBUS4-Pad43)") (class "Default")
      (node (ref "U2") (pin "43") (pinfunction "BDBUS4_43") (pintype "bidirectional"))
    )
    (net (code "167") (name "unconnected-(U2-BDBUS5-Pad44)") (class "Default")
      (node (ref "U2") (pin "44") (pinfunction "BDBUS5_44") (pintype "bidirectional"))
    )
    (net (code "168") (name "unconnected-(U2-BDBUS6-Pad45)") (class "Default")
      (node (ref "U2") (pin "45") (pinfunction "BDBUS6_45") (pintype "bidirectional"))
    )
    (net (code "169") (name "unconnected-(U2-BDBUS7-Pad46)") (class "Default")
      (node (ref "U2") (pin "46") (pinfunction "BDBUS7_46") (pintype "bidirectional"))
    )
    (net (code "170") (name "unconnected-(U3-NC-Pad7)") (class "Default")
      (node (ref "U3") (pin "7") (pinfunction "NC_7") (pintype "bidirectional"))
    )
    (net (code "171") (name "unconnected-(U4-IO12_15-PadG10)") (class "Default")
      (node (ref "U4") (pin "G10") (pinfunction "IO12_15_G10") (pintype "bidirectional"))
    )
    (net (code "172") (name "unconnected-(U4-IO21_15-PadC10)") (class "Default")
      (node (ref "U4") (pin "C10") (pinfunction "IO21_15_C10") (pintype "bidirectional"))
    )
    (net (code "173") (name "unconnected-(U4-IO21_16-PadE8)") (class "Default")
      (node (ref "U4") (pin "E8") (pinfunction "IO21_16_E8") (pintype "bidirectional"))
    )
    (net (code "174") (name "unconnected-(U4-NC1-PadD8)") (class "Default")
      (node (ref "U4") (pin "D8") (pinfunction "NC1_D8") (pintype "bidirectional"))
    )
    (net (code "175") (name "unconnected-(U4-NC2-PadE10)") (class "Default")
      (node (ref "U4") (pin "E10") (pinfunction "NC2_E10") (pintype "bidirectional"))
    )
    (net (code "176") (name "unconnected-(U4-NC3-PadH7)") (class "Default")
      (node (ref "U4") (pin "H7") (pinfunction "NC3_H7") (pintype "bidirectional"))
    )
    (net (code "177") (name "unconnected-(U4-NC4-PadK4)") (class "Default")
      (node (ref "U4") (pin "K4") (pinfunction "NC4_K4") (pintype "bidirectional"))
    )
    (net (code "178") (name "unconnected-(U4-NC5-PadK6)") (class "Default")
      (node (ref "U4") (pin "K6") (pinfunction "NC5_K6") (pintype "bidirectional"))
    )
    (net (code "179") (name "unconnected-(U4-NC6-PadA4)") (class "Default")
      (node (ref "U4") (pin "A4") (pinfunction "NC6_A4") (pintype "bidirectional"))
    )
    (net (code "180") (name "unconnected-(U4-NC7-PadA5)") (class "Default")
      (node (ref "U4") (pin "A5") (pinfunction "NC7_A5") (pintype "bidirectional"))
    )
    (net (code "181") (name "unconnected-(U4-NC8-PadA7)") (class "Default")
      (node (ref "U4") (pin "A7") (pinfunction "NC8_A7") (pintype "bidirectional"))
    )
    (net (code "182") (name "unconnected-(U4-NC9-PadA8)") (class "Default")
      (node (ref "U4") (pin "A8") (pinfunction "NC9_A8") (pintype "bidirectional"))
    )
    (net (code "183") (name "unconnected-(U4-NC10-PadA9)") (class "Default")
      (node (ref "U4") (pin "A9") (pinfunction "NC10_A9") (pintype "bidirectional"))
    )
    (net (code "184") (name "unconnected-(U4-NC11-PadC3)") (class "Default")
      (node (ref "U4") (pin "C3") (pinfunction "NC11_C3") (pintype "bidirectional"))
    )
    (net (code "185") (name "unconnected-(U4-NC12-PadK7)") (class "Default")
      (node (ref "U4") (pin "K7") (pinfunction "NC12_K7") (pintype "bidirectional"))
    )
    (net (code "186") (name "unconnected-(U5A-FLTP1-Pad3)") (class "Default")
      (node (ref "U5") (pin "3") (pinfunction "FLTP1_3") (pintype "bidirectional"))
    )
    (net (code "187") (name "unconnected-(U5A-FLTP2-Pad4)") (class "Default")
      (node (ref "U5") (pin "4") (pinfunction "FLTP2_4") (pintype "bidirectional"))
    )
    (net (code "188") (name "unconnected-(U6-NC-Pad2)") (class "Default")
      (node (ref "U6") (pin "2") (pinfunction "NC_2") (pintype "bidirectional"))
    )
    (net (code "189") (name "unconnected-(Y2-PadP$2)") (class "Default")
      (node (ref "Y2") (pin "P$2") (pinfunction "P$2_P$2") (pintype "bidirectional"))
    )
    (net (code "190") (name "unconnected-(Y2-PadP$4)") (class "Default")
      (node (ref "Y2") (pin "P$4") (pinfunction "P$4_P$4") (pintype "bidirectional"))
    )
  )
)
